# DE-130817_03.net
KiCad netlist of a schematic drawn in Altium Designer
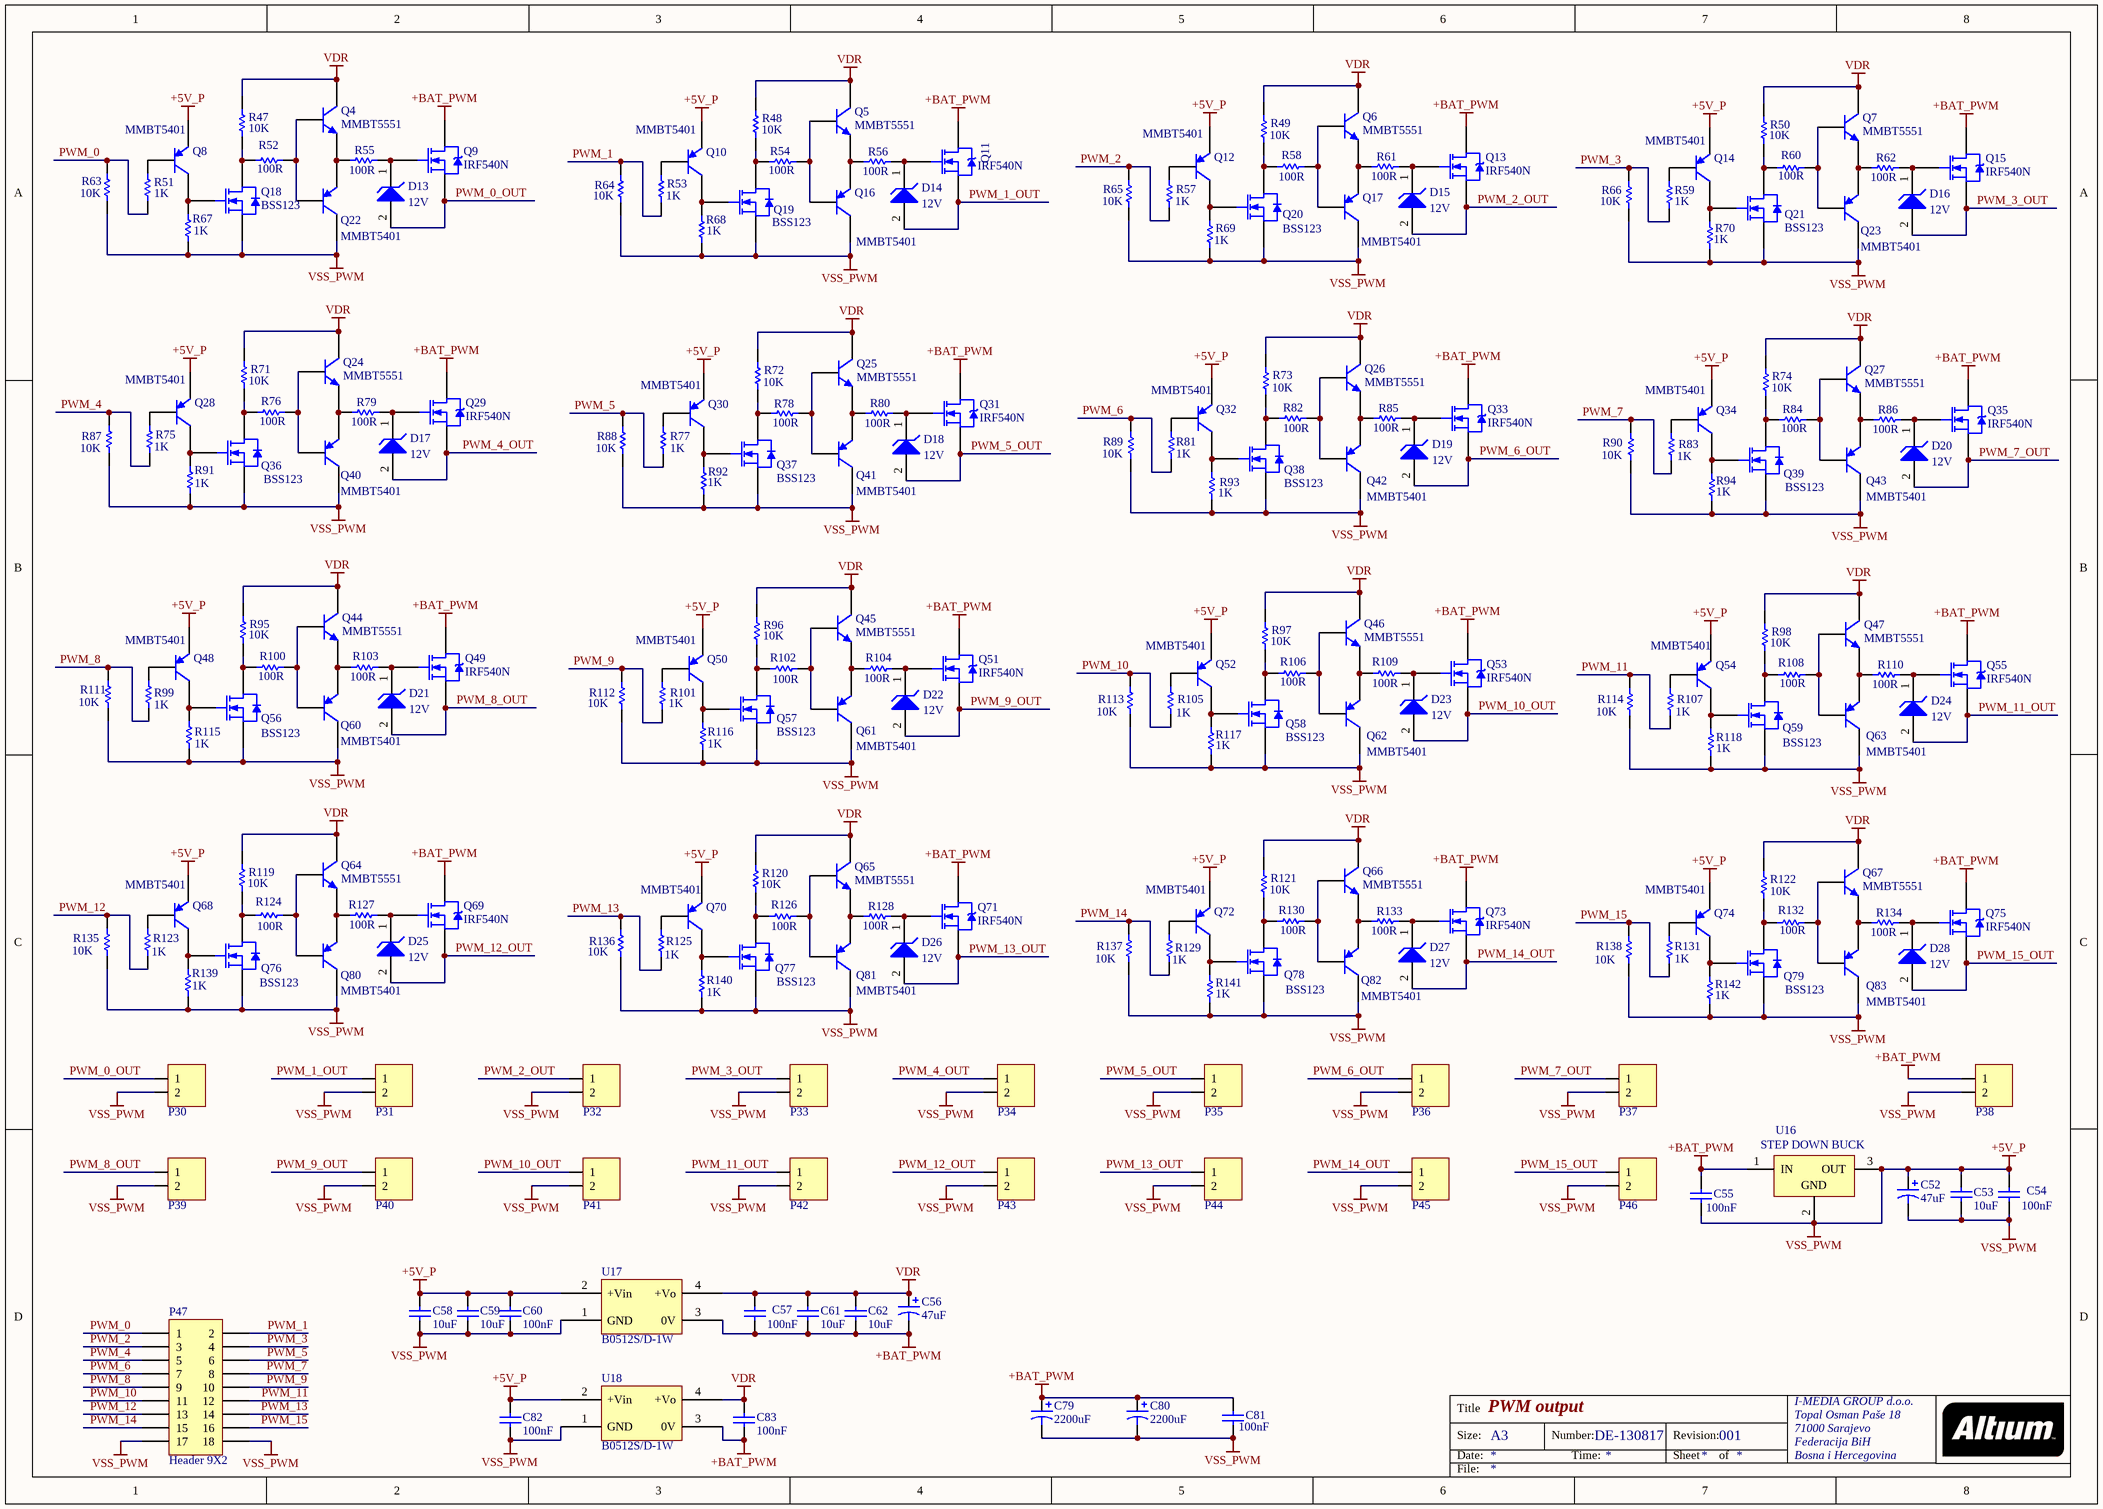
[diagram p0: DE-130817_03.SchDoc]

(export (version "E")
  (design (tool "Eeschema 10.0.6"))
  (components
    (comp (ref "C52")
      (value "47uF")
      (footprint "CAPPR2-5X11")
      (description "Aluminum Electrolytic Capacitor, Radial Style with Long Leads: 47uF, 35V")
      (fields (field (name "Comment") "EKA00AA247F00") (field (name "PUBLISHER") "Altium Limited"))
      (libsource (lib "Vishay Roederstein Electrolytic Radial-Lead Capacitor") (part "EKA00AA247F00"))
    )
    (comp (ref "C53")
      (value "10uF")
      (footprint "0805")
      (description "Ceramic Chip Capacitor - Standard")
      (fields (field (name "PUBLISHER") "Altium Limited"))
      (libsource (lib "DE-130817") (part "C0805"))
    )
    (comp (ref "C54")
      (value "100nF")
      (footprint "0603")
      (description "Ceramic Chip Capacitor - Standard")
      (fields (field (name "PUBLISHER") "Altium Limited"))
      (libsource (lib "DE-130817") (part "C0603"))
    )
    (comp (ref "C55")
      (value "100nF")
      (footprint "VP52-2.5")
      (description "Dipped Radial Multilayer Ceramic Capacitor X7R: 100nF")
      (fields (field (name "Comment") "VP52BY104") (field (name "PUBLISHER") "Altium Limited"))
      (libsource (lib "Vishay Vitramon Ceramic Dipped Capacitor") (part "VP52BY104"))
    )
    (comp (ref "C56")
      (value "47uF")
      (footprint "CAPPR2-5X11")
      (description "Aluminum Electrolytic Capacitor, Radial Style with Long Leads: 47uF, 35V")
      (fields (field (name "Comment") "EKA00AA247F00") (field (name "PUBLISHER") "Altium Limited"))
      (libsource (lib "Vishay Roederstein Electrolytic Radial-Lead Capacitor") (part "EKA00AA247F00"))
    )
    (comp (ref "C57")
      (value "100nF")
      (footprint "0603")
      (description "Ceramic Chip Capacitor - Standard")
      (fields (field (name "PUBLISHER") "Altium Limited"))
      (libsource (lib "DE-130817") (part "C0603"))
    )
    (comp (ref "C58")
      (value "10uF")
      (footprint "0805")
      (description "Ceramic Chip Capacitor - Standard")
      (fields (field (name "PUBLISHER") "Altium Limited"))
      (libsource (lib "DE-130817") (part "C0805"))
    )
    (comp (ref "C59")
      (value "10uF")
      (footprint "0805")
      (description "Ceramic Chip Capacitor - Standard")
      (fields (field (name "PUBLISHER") "Altium Limited"))
      (libsource (lib "DE-130817") (part "C0805"))
    )
    (comp (ref "C60")
      (value "100nF")
      (footprint "0603")
      (description "Ceramic Chip Capacitor - Standard")
      (fields (field (name "PUBLISHER") "Altium Limited"))
      (libsource (lib "DE-130817") (part "C0603"))
    )
    (comp (ref "C61")
      (value "10uF")
      (footprint "0805")
      (description "Ceramic Chip Capacitor - Standard")
      (fields (field (name "PUBLISHER") "Altium Limited"))
      (libsource (lib "DE-130817") (part "C0805"))
    )
    (comp (ref "C62")
      (value "10uF")
      (footprint "0805")
      (description "Ceramic Chip Capacitor - Standard")
      (fields (field (name "PUBLISHER") "Altium Limited"))
      (libsource (lib "DE-130817") (part "C0805"))
    )
    (comp (ref "C79")
      (value "2200uF")
      (footprint "CAPPR7.5-16X35.5")
      (description "Aluminum Electrolytic Capacitor, Radial Style with Long Leads: 2200uF, 50V")
      (fields (field (name "Comment") "EKA00JL422H00") (field (name "PUBLISHER") "Altium Limited"))
      (libsource (lib "Vishay Roederstein Electrolytic Radial-Lead Capacitor") (part "EKA00JL422H00"))
    )
    (comp (ref "C80")
      (value "2200uF")
      (footprint "CAPPR7.5-16X35.5")
      (description "Aluminum Electrolytic Capacitor, Radial Style with Long Leads: 2200uF, 50V")
      (fields (field (name "Comment") "EKA00JL422H00") (field (name "PUBLISHER") "Altium Limited"))
      (libsource (lib "Vishay Roederstein Electrolytic Radial-Lead Capacitor") (part "EKA00JL422H00"))
    )
    (comp (ref "C81")
      (value "100nF")
      (footprint "VP60-3.6")
      (description "Dipped Radial Multilayer Ceramic Capacitor COG (NPO): 100nF, 100V")
      (fields (field (name "Comment") "VP60BA104FB") (field (name "PUBLISHER") "Altium Limited"))
      (libsource (lib "Vishay Vitramon Ceramic Dipped Capacitor") (part "VP60BA104FB"))
    )
    (comp (ref "C82")
      (value "100nF")
      (footprint "0603")
      (description "Ceramic Chip Capacitor - Standard")
      (fields (field (name "PUBLISHER") "Altium Limited"))
      (libsource (lib "DE-130817") (part "C0603"))
    )
    (comp (ref "C83")
      (value "100nF")
      (footprint "0603")
      (description "Ceramic Chip Capacitor - Standard")
      (fields (field (name "PUBLISHER") "Altium Limited"))
      (libsource (lib "DE-130817") (part "C0603"))
    )
    (comp (ref "D13")
      (value "12V")
      (footprint "ONSC-SOD-123-2-425-04_V")
      (description "Zener Voltage Regulator, 500 mW, 2-Pin SOD-123, Pb-Free, Tape and Reel")
      (fields (field (name "MANUFACTURER") "On Semiconductor") (field (name "PARTNUMBER") "SZMMSZ12T1G"))
      (libsource (lib "ON Semi Zener Diodes") (part "SZMMSZ12T1G"))
    )
    (comp (ref "D14")
      (value "12V")
      (footprint "ONSC-SOD-123-2-425-04_V")
      (description "Zener Voltage Regulator, 500 mW, 2-Pin SOD-123, Pb-Free, Tape and Reel")
      (fields (field (name "MANUFACTURER") "On Semiconductor") (field (name "PARTNUMBER") "SZMMSZ12T1G"))
      (libsource (lib "ON Semi Zener Diodes") (part "SZMMSZ12T1G"))
    )
    (comp (ref "D15")
      (value "12V")
      (footprint "ONSC-SOD-123-2-425-04_V")
      (description "Zener Voltage Regulator, 500 mW, 2-Pin SOD-123, Pb-Free, Tape and Reel")
      (fields (field (name "MANUFACTURER") "On Semiconductor") (field (name "PARTNUMBER") "SZMMSZ12T1G"))
      (libsource (lib "ON Semi Zener Diodes") (part "SZMMSZ12T1G"))
    )
    (comp (ref "D16")
      (value "12V")
      (footprint "ONSC-SOD-123-2-425-04_V")
      (description "Zener Voltage Regulator, 500 mW, 2-Pin SOD-123, Pb-Free, Tape and Reel")
      (fields (field (name "MANUFACTURER") "On Semiconductor") (field (name "PARTNUMBER") "SZMMSZ12T1G"))
      (libsource (lib "ON Semi Zener Diodes") (part "SZMMSZ12T1G"))
    )
    (comp (ref "D17")
      (value "12V")
      (footprint "ONSC-SOD-123-2-425-04_V")
      (description "Zener Voltage Regulator, 500 mW, 2-Pin SOD-123, Pb-Free, Tape and Reel")
      (fields (field (name "MANUFACTURER") "On Semiconductor") (field (name "PARTNUMBER") "SZMMSZ12T1G"))
      (libsource (lib "ON Semi Zener Diodes") (part "SZMMSZ12T1G"))
    )
    (comp (ref "D18")
      (value "12V")
      (footprint "ONSC-SOD-123-2-425-04_V")
      (description "Zener Voltage Regulator, 500 mW, 2-Pin SOD-123, Pb-Free, Tape and Reel")
      (fields (field (name "MANUFACTURER") "On Semiconductor") (field (name "PARTNUMBER") "SZMMSZ12T1G"))
      (libsource (lib "ON Semi Zener Diodes") (part "SZMMSZ12T1G"))
    )
    (comp (ref "D19")
      (value "12V")
      (footprint "ONSC-SOD-123-2-425-04_V")
      (description "Zener Voltage Regulator, 500 mW, 2-Pin SOD-123, Pb-Free, Tape and Reel")
      (fields (field (name "MANUFACTURER") "On Semiconductor") (field (name "PARTNUMBER") "SZMMSZ12T1G"))
      (libsource (lib "ON Semi Zener Diodes") (part "SZMMSZ12T1G"))
    )
    (comp (ref "D20")
      (value "12V")
      (footprint "ONSC-SOD-123-2-425-04_V")
      (description "Zener Voltage Regulator, 500 mW, 2-Pin SOD-123, Pb-Free, Tape and Reel")
      (fields (field (name "MANUFACTURER") "On Semiconductor") (field (name "PARTNUMBER") "SZMMSZ12T1G"))
      (libsource (lib "ON Semi Zener Diodes") (part "SZMMSZ12T1G"))
    )
    (comp (ref "D21")
      (value "12V")
      (footprint "ONSC-SOD-123-2-425-04_V")
      (description "Zener Voltage Regulator, 500 mW, 2-Pin SOD-123, Pb-Free, Tape and Reel")
      (fields (field (name "MANUFACTURER") "On Semiconductor") (field (name "PARTNUMBER") "SZMMSZ12T1G"))
      (libsource (lib "ON Semi Zener Diodes") (part "SZMMSZ12T1G"))
    )
    (comp (ref "D22")
      (value "12V")
      (footprint "ONSC-SOD-123-2-425-04_V")
      (description "Zener Voltage Regulator, 500 mW, 2-Pin SOD-123, Pb-Free, Tape and Reel")
      (fields (field (name "MANUFACTURER") "On Semiconductor") (field (name "PARTNUMBER") "SZMMSZ12T1G"))
      (libsource (lib "ON Semi Zener Diodes") (part "SZMMSZ12T1G"))
    )
    (comp (ref "D23")
      (value "12V")
      (footprint "ONSC-SOD-123-2-425-04_V")
      (description "Zener Voltage Regulator, 500 mW, 2-Pin SOD-123, Pb-Free, Tape and Reel")
      (fields (field (name "MANUFACTURER") "On Semiconductor") (field (name "PARTNUMBER") "SZMMSZ12T1G"))
      (libsource (lib "ON Semi Zener Diodes") (part "SZMMSZ12T1G"))
    )
    (comp (ref "D24")
      (value "12V")
      (footprint "ONSC-SOD-123-2-425-04_V")
      (description "Zener Voltage Regulator, 500 mW, 2-Pin SOD-123, Pb-Free, Tape and Reel")
      (fields (field (name "MANUFACTURER") "On Semiconductor") (field (name "PARTNUMBER") "SZMMSZ12T1G"))
      (libsource (lib "ON Semi Zener Diodes") (part "SZMMSZ12T1G"))
    )
    (comp (ref "D25")
      (value "12V")
      (footprint "ONSC-SOD-123-2-425-04_V")
      (description "Zener Voltage Regulator, 500 mW, 2-Pin SOD-123, Pb-Free, Tape and Reel")
      (fields (field (name "MANUFACTURER") "On Semiconductor") (field (name "PARTNUMBER") "SZMMSZ12T1G"))
      (libsource (lib "ON Semi Zener Diodes") (part "SZMMSZ12T1G"))
    )
    (comp (ref "D26")
      (value "12V")
      (footprint "ONSC-SOD-123-2-425-04_V")
      (description "Zener Voltage Regulator, 500 mW, 2-Pin SOD-123, Pb-Free, Tape and Reel")
      (fields (field (name "MANUFACTURER") "On Semiconductor") (field (name "PARTNUMBER") "SZMMSZ12T1G"))
      (libsource (lib "ON Semi Zener Diodes") (part "SZMMSZ12T1G"))
    )
    (comp (ref "D27")
      (value "12V")
      (footprint "ONSC-SOD-123-2-425-04_V")
      (description "Zener Voltage Regulator, 500 mW, 2-Pin SOD-123, Pb-Free, Tape and Reel")
      (fields (field (name "MANUFACTURER") "On Semiconductor") (field (name "PARTNUMBER") "SZMMSZ12T1G"))
      (libsource (lib "ON Semi Zener Diodes") (part "SZMMSZ12T1G"))
    )
    (comp (ref "D28")
      (value "12V")
      (footprint "ONSC-SOD-123-2-425-04_V")
      (description "Zener Voltage Regulator, 500 mW, 2-Pin SOD-123, Pb-Free, Tape and Reel")
      (fields (field (name "MANUFACTURER") "On Semiconductor") (field (name "PARTNUMBER") "SZMMSZ12T1G"))
      (libsource (lib "ON Semi Zener Diodes") (part "SZMMSZ12T1G"))
    )
    (comp (ref "P30")
      (value "TERMINAL BLOK 2")
      (footprint "TERMINAL BLOK 2")
      (description "2 pinski terminal blok")
      (libsource (lib "DE-130817") (part "TERMINAL BLOK 2"))
    )
    (comp (ref "P31")
      (value "TERMINAL BLOK 2")
      (footprint "TERMINAL BLOK 2")
      (description "2 pinski terminal blok")
      (libsource (lib "DE-130817") (part "TERMINAL BLOK 2"))
    )
    (comp (ref "P32")
      (value "TERMINAL BLOK 2")
      (footprint "TERMINAL BLOK 2")
      (description "2 pinski terminal blok")
      (libsource (lib "DE-130817") (part "TERMINAL BLOK 2"))
    )
    (comp (ref "P33")
      (value "TERMINAL BLOK 2")
      (footprint "TERMINAL BLOK 2")
      (description "2 pinski terminal blok")
      (libsource (lib "DE-130817") (part "TERMINAL BLOK 2"))
    )
    (comp (ref "P34")
      (value "TERMINAL BLOK 2")
      (footprint "TERMINAL BLOK 2")
      (description "2 pinski terminal blok")
      (libsource (lib "DE-130817") (part "TERMINAL BLOK 2"))
    )
    (comp (ref "P35")
      (value "TERMINAL BLOK 2")
      (footprint "TERMINAL BLOK 2")
      (description "2 pinski terminal blok")
      (libsource (lib "") (part "TERMINAL BLOK 2_3"))
    )
    (comp (ref "P36")
      (value "TERMINAL BLOK 2")
      (footprint "TERMINAL BLOK 2")
      (description "2 pinski terminal blok")
      (libsource (lib "") (part "TERMINAL BLOK 2_3"))
    )
    (comp (ref "P37")
      (value "TERMINAL BLOK 2")
      (footprint "TERMINAL BLOK 2")
      (description "2 pinski terminal blok")
      (libsource (lib "") (part "TERMINAL BLOK 2_3"))
    )
    (comp (ref "P38")
      (value "TERMINAL BLOK 2")
      (footprint "TERMINAL BLOK 2")
      (description "2 pinski terminal blok")
      (libsource (lib "") (part "TERMINAL BLOK 2_3"))
    )
    (comp (ref "P39")
      (value "TERMINAL BLOK 2")
      (footprint "TERMINAL BLOK 2")
      (description "2 pinski terminal blok")
      (libsource (lib "") (part "TERMINAL BLOK 2_1"))
    )
    (comp (ref "P40")
      (value "TERMINAL BLOK 2")
      (footprint "TERMINAL BLOK 2")
      (description "2 pinski terminal blok")
      (libsource (lib "") (part "TERMINAL BLOK 2_1"))
    )
    (comp (ref "P41")
      (value "TERMINAL BLOK 2")
      (footprint "TERMINAL BLOK 2")
      (description "2 pinski terminal blok")
      (libsource (lib "") (part "TERMINAL BLOK 2_1"))
    )
    (comp (ref "P42")
      (value "TERMINAL BLOK 2")
      (footprint "TERMINAL BLOK 2")
      (description "2 pinski terminal blok")
      (libsource (lib "") (part "TERMINAL BLOK 2_1"))
    )
    (comp (ref "P43")
      (value "TERMINAL BLOK 2")
      (footprint "TERMINAL BLOK 2")
      (description "2 pinski terminal blok")
      (libsource (lib "") (part "TERMINAL BLOK 2_1"))
    )
    (comp (ref "P44")
      (value "TERMINAL BLOK 2")
      (footprint "TERMINAL BLOK 2")
      (description "2 pinski terminal blok")
      (libsource (lib "") (part "TERMINAL BLOK 2_2"))
    )
    (comp (ref "P45")
      (value "TERMINAL BLOK 2")
      (footprint "TERMINAL BLOK 2")
      (description "2 pinski terminal blok")
      (libsource (lib "") (part "TERMINAL BLOK 2_2"))
    )
    (comp (ref "P46")
      (value "TERMINAL BLOK 2")
      (footprint "TERMINAL BLOK 2")
      (description "2 pinski terminal blok")
      (libsource (lib "") (part "TERMINAL BLOK 2_2"))
    )
    (comp (ref "P47")
      (value "Header 9X2")
      (footprint "HDR2X9")
      (description "Header, 9-Pin, Dual row")
      (fields (field (name "PUBLISHER") "Altium Limited"))
      (libsource (lib "Miscellaneous Connectors") (part "Header 9X2"))
    )
    (comp (ref "Q4")
      (value "MMBT5551")
      (footprint "SOT23_N")
      (description "NPN General-purpose Transistor")
      (fields (field (name "PUBLISHER") "Altium Limited"))
      (libsource (lib "DE-130817") (part "BC817"))
    )
    (comp (ref "Q5")
      (value "MMBT5551")
      (footprint "SOT23_N")
      (description "NPN General-purpose Transistor")
      (fields (field (name "PUBLISHER") "Altium Limited"))
      (libsource (lib "DE-130817") (part "BC817"))
    )
    (comp (ref "Q6")
      (value "MMBT5551")
      (footprint "SOT23_N")
      (description "NPN General-purpose Transistor")
      (fields (field (name "PUBLISHER") "Altium Limited"))
      (libsource (lib "DE-130817") (part "BC817"))
    )
    (comp (ref "Q7")
      (value "MMBT5551")
      (footprint "SOT23_N")
      (description "NPN General-purpose Transistor")
      (fields (field (name "PUBLISHER") "Altium Limited"))
      (libsource (lib "DE-130817") (part "BC817"))
    )
    (comp (ref "Q8")
      (value "MMBT5401")
      (footprint "SOT23_N")
      (description "PNP General-purpose Transistor")
      (fields (field (name "PUBLISHER") "Altium Limited"))
      (libsource (lib "DE-130817") (part "BC807"))
    )
    (comp (ref "Q9")
      (value "IRF540N")
      (footprint "TO-220AB")
      (description "HEXFET Power MOSFET")
      (fields (field (name "PUBLISHER") "Altium Limited"))
      (libsource (lib "IR Discrete MOSFET - Power") (part "IRF540N"))
    )
    (comp (ref "Q10")
      (value "MMBT5401")
      (footprint "SOT23_N")
      (description "PNP General-purpose Transistor")
      (fields (field (name "PUBLISHER") "Altium Limited"))
      (libsource (lib "DE-130817") (part "BC807"))
    )
    (comp (ref "Q11")
      (value "IRF540N")
      (footprint "TO-220AB")
      (description "HEXFET Power MOSFET")
      (fields (field (name "PUBLISHER") "Altium Limited"))
      (libsource (lib "IR Discrete MOSFET - Power") (part "IRF540N"))
    )
    (comp (ref "Q12")
      (value "MMBT5401")
      (footprint "SOT23_N")
      (description "PNP General-purpose Transistor")
      (fields (field (name "PUBLISHER") "Altium Limited"))
      (libsource (lib "DE-130817") (part "BC807"))
    )
    (comp (ref "Q13")
      (value "IRF540N")
      (footprint "TO-220AB")
      (description "HEXFET Power MOSFET")
      (fields (field (name "PUBLISHER") "Altium Limited"))
      (libsource (lib "IR Discrete MOSFET - Power") (part "IRF540N"))
    )
    (comp (ref "Q14")
      (value "MMBT5401")
      (footprint "SOT23_N")
      (description "PNP General-purpose Transistor")
      (fields (field (name "PUBLISHER") "Altium Limited"))
      (libsource (lib "DE-130817") (part "BC807"))
    )
    (comp (ref "Q15")
      (value "IRF540N")
      (footprint "TO-220AB")
      (description "HEXFET Power MOSFET")
      (fields (field (name "PUBLISHER") "Altium Limited"))
      (libsource (lib "IR Discrete MOSFET - Power") (part "IRF540N"))
    )
    (comp (ref "Q16")
      (value "MMBT5401")
      (footprint "SOT23_N")
      (description "PNP General-purpose Transistor")
      (fields (field (name "PUBLISHER") "Altium Limited"))
      (libsource (lib "DE-130817") (part "BC807"))
    )
    (comp (ref "Q17")
      (value "MMBT5401")
      (footprint "SOT23_N")
      (description "PNP General-purpose Transistor")
      (fields (field (name "PUBLISHER") "Altium Limited"))
      (libsource (lib "DE-130817") (part "BC807"))
    )
    (comp (ref "Q18")
      (value "BSS123")
      (footprint "SOT23_N")
      (description "N-channel Enhancement Mode Vertical D-MOSFET")
      (fields (field (name "PUBLISHER") "Altium Limited"))
      (libsource (lib "sch_library") (part "BSS123"))
    )
    (comp (ref "Q19")
      (value "BSS123")
      (footprint "SOT23_N")
      (description "N-channel Enhancement Mode Vertical D-MOSFET")
      (fields (field (name "PUBLISHER") "Altium Limited"))
      (libsource (lib "sch_library") (part "BSS123"))
    )
    (comp (ref "Q20")
      (value "BSS123")
      (footprint "SOT23_N")
      (description "N-channel Enhancement Mode Vertical D-MOSFET")
      (fields (field (name "PUBLISHER") "Altium Limited"))
      (libsource (lib "sch_library") (part "BSS123"))
    )
    (comp (ref "Q21")
      (value "BSS123")
      (footprint "SOT23_N")
      (description "N-channel Enhancement Mode Vertical D-MOSFET")
      (fields (field (name "PUBLISHER") "Altium Limited"))
      (libsource (lib "sch_library") (part "BSS123"))
    )
    (comp (ref "Q22")
      (value "MMBT5401")
      (footprint "SOT23_N")
      (description "PNP General-purpose Transistor")
      (fields (field (name "PUBLISHER") "Altium Limited"))
      (libsource (lib "DE-130817") (part "BC807"))
    )
    (comp (ref "Q23")
      (value "MMBT5401")
      (footprint "SOT23_N")
      (description "PNP General-purpose Transistor")
      (fields (field (name "PUBLISHER") "Altium Limited"))
      (libsource (lib "DE-130817") (part "BC807"))
    )
    (comp (ref "Q24")
      (value "MMBT5551")
      (footprint "SOT23_N")
      (description "NPN General-purpose Transistor")
      (fields (field (name "PUBLISHER") "Altium Limited"))
      (libsource (lib "DE-130817") (part "BC817"))
    )
    (comp (ref "Q25")
      (value "MMBT5551")
      (footprint "SOT23_N")
      (description "NPN General-purpose Transistor")
      (fields (field (name "PUBLISHER") "Altium Limited"))
      (libsource (lib "DE-130817") (part "BC817"))
    )
    (comp (ref "Q26")
      (value "MMBT5551")
      (footprint "SOT23_N")
      (description "NPN General-purpose Transistor")
      (fields (field (name "PUBLISHER") "Altium Limited"))
      (libsource (lib "DE-130817") (part "BC817"))
    )
    (comp (ref "Q27")
      (value "MMBT5551")
      (footprint "SOT23_N")
      (description "NPN General-purpose Transistor")
      (fields (field (name "PUBLISHER") "Altium Limited"))
      (libsource (lib "DE-130817") (part "BC817"))
    )
    (comp (ref "Q28")
      (value "MMBT5401")
      (footprint "SOT23_N")
      (description "PNP General-purpose Transistor")
      (fields (field (name "PUBLISHER") "Altium Limited"))
      (libsource (lib "DE-130817") (part "BC807"))
    )
    (comp (ref "Q29")
      (value "IRF540N")
      (footprint "TO-220AB")
      (description "HEXFET Power MOSFET")
      (fields (field (name "PUBLISHER") "Altium Limited"))
      (libsource (lib "IR Discrete MOSFET - Power") (part "IRF540N"))
    )
    (comp (ref "Q30")
      (value "MMBT5401")
      (footprint "SOT23_N")
      (description "PNP General-purpose Transistor")
      (fields (field (name "PUBLISHER") "Altium Limited"))
      (libsource (lib "DE-130817") (part "BC807"))
    )
    (comp (ref "Q31")
      (value "IRF540N")
      (footprint "TO-220AB")
      (description "HEXFET Power MOSFET")
      (fields (field (name "PUBLISHER") "Altium Limited"))
      (libsource (lib "IR Discrete MOSFET - Power") (part "IRF540N"))
    )
    (comp (ref "Q32")
      (value "MMBT5401")
      (footprint "SOT23_N")
      (description "PNP General-purpose Transistor")
      (fields (field (name "PUBLISHER") "Altium Limited"))
      (libsource (lib "DE-130817") (part "BC807"))
    )
    (comp (ref "Q33")
      (value "IRF540N")
      (footprint "TO-220AB")
      (description "HEXFET Power MOSFET")
      (fields (field (name "PUBLISHER") "Altium Limited"))
      (libsource (lib "IR Discrete MOSFET - Power") (part "IRF540N"))
    )
    (comp (ref "Q34")
      (value "MMBT5401")
      (footprint "SOT23_N")
      (description "PNP General-purpose Transistor")
      (fields (field (name "PUBLISHER") "Altium Limited"))
      (libsource (lib "DE-130817") (part "BC807"))
    )
    (comp (ref "Q35")
      (value "IRF540N")
      (footprint "TO-220AB")
      (description "HEXFET Power MOSFET")
      (fields (field (name "PUBLISHER") "Altium Limited"))
      (libsource (lib "IR Discrete MOSFET - Power") (part "IRF540N"))
    )
    (comp (ref "Q36")
      (value "BSS123")
      (footprint "SOT23_N")
      (description "N-channel Enhancement Mode Vertical D-MOSFET")
      (fields (field (name "PUBLISHER") "Altium Limited"))
      (libsource (lib "sch_library") (part "BSS123"))
    )
    (comp (ref "Q37")
      (value "BSS123")
      (footprint "SOT23_N")
      (description "N-channel Enhancement Mode Vertical D-MOSFET")
      (fields (field (name "PUBLISHER") "Altium Limited"))
      (libsource (lib "sch_library") (part "BSS123"))
    )
    (comp (ref "Q38")
      (value "BSS123")
      (footprint "SOT23_N")
      (description "N-channel Enhancement Mode Vertical D-MOSFET")
      (fields (field (name "PUBLISHER") "Altium Limited"))
      (libsource (lib "sch_library") (part "BSS123"))
    )
    (comp (ref "Q39")
      (value "BSS123")
      (footprint "SOT23_N")
      (description "N-channel Enhancement Mode Vertical D-MOSFET")
      (fields (field (name "PUBLISHER") "Altium Limited"))
      (libsource (lib "sch_library") (part "BSS123"))
    )
    (comp (ref "Q40")
      (value "MMBT5401")
      (footprint "SOT23_N")
      (description "PNP General-purpose Transistor")
      (fields (field (name "PUBLISHER") "Altium Limited"))
      (libsource (lib "DE-130817") (part "BC807"))
    )
    (comp (ref "Q41")
      (value "MMBT5401")
      (footprint "SOT23_N")
      (description "PNP General-purpose Transistor")
      (fields (field (name "PUBLISHER") "Altium Limited"))
      (libsource (lib "DE-130817") (part "BC807"))
    )
    (comp (ref "Q42")
      (value "MMBT5401")
      (footprint "SOT23_N")
      (description "PNP General-purpose Transistor")
      (fields (field (name "PUBLISHER") "Altium Limited"))
      (libsource (lib "DE-130817") (part "BC807"))
    )
    (comp (ref "Q43")
      (value "MMBT5401")
      (footprint "SOT23_N")
      (description "PNP General-purpose Transistor")
      (fields (field (name "PUBLISHER") "Altium Limited"))
      (libsource (lib "DE-130817") (part "BC807"))
    )
    (comp (ref "Q44")
      (value "MMBT5551")
      (footprint "SOT23_N")
      (description "NPN General-purpose Transistor")
      (fields (field (name "PUBLISHER") "Altium Limited"))
      (libsource (lib "DE-130817") (part "BC817"))
    )
    (comp (ref "Q45")
      (value "MMBT5551")
      (footprint "SOT23_N")
      (description "NPN General-purpose Transistor")
      (fields (field (name "PUBLISHER") "Altium Limited"))
      (libsource (lib "DE-130817") (part "BC817"))
    )
    (comp (ref "Q46")
      (value "MMBT5551")
      (footprint "SOT23_N")
      (description "NPN General-purpose Transistor")
      (fields (field (name "PUBLISHER") "Altium Limited"))
      (libsource (lib "DE-130817") (part "BC817"))
    )
    (comp (ref "Q47")
      (value "MMBT5551")
      (footprint "SOT23_N")
      (description "NPN General-purpose Transistor")
      (fields (field (name "PUBLISHER") "Altium Limited"))
      (libsource (lib "DE-130817") (part "BC817"))
    )
    (comp (ref "Q48")
      (value "MMBT5401")
      (footprint "SOT23_N")
      (description "PNP General-purpose Transistor")
      (fields (field (name "PUBLISHER") "Altium Limited"))
      (libsource (lib "DE-130817") (part "BC807"))
    )
    (comp (ref "Q49")
      (value "IRF540N")
      (footprint "TO-220AB")
      (description "HEXFET Power MOSFET")
      (fields (field (name "PUBLISHER") "Altium Limited"))
      (libsource (lib "IR Discrete MOSFET - Power") (part "IRF540N"))
    )
    (comp (ref "Q50")
      (value "MMBT5401")
      (footprint "SOT23_N")
      (description "PNP General-purpose Transistor")
      (fields (field (name "PUBLISHER") "Altium Limited"))
      (libsource (lib "DE-130817") (part "BC807"))
    )
    (comp (ref "Q51")
      (value "IRF540N")
      (footprint "TO-220AB")
      (description "HEXFET Power MOSFET")
      (fields (field (name "PUBLISHER") "Altium Limited"))
      (libsource (lib "IR Discrete MOSFET - Power") (part "IRF540N"))
    )
    (comp (ref "Q52")
      (value "MMBT5401")
      (footprint "SOT23_N")
      (description "PNP General-purpose Transistor")
      (fields (field (name "PUBLISHER") "Altium Limited"))
      (libsource (lib "DE-130817") (part "BC807"))
    )
    (comp (ref "Q53")
      (value "IRF540N")
      (footprint "TO-220AB")
      (description "HEXFET Power MOSFET")
      (fields (field (name "PUBLISHER") "Altium Limited"))
      (libsource (lib "IR Discrete MOSFET - Power") (part "IRF540N"))
    )
    (comp (ref "Q54")
      (value "MMBT5401")
      (footprint "SOT23_N")
      (description "PNP General-purpose Transistor")
      (fields (field (name "PUBLISHER") "Altium Limited"))
      (libsource (lib "DE-130817") (part "BC807"))
    )
    (comp (ref "Q55")
      (value "IRF540N")
      (footprint "TO-220AB")
      (description "HEXFET Power MOSFET")
      (fields (field (name "PUBLISHER") "Altium Limited"))
      (libsource (lib "IR Discrete MOSFET - Power") (part "IRF540N"))
    )
    (comp (ref "Q56")
      (value "BSS123")
      (footprint "SOT23_N")
      (description "N-channel Enhancement Mode Vertical D-MOSFET")
      (fields (field (name "PUBLISHER") "Altium Limited"))
      (libsource (lib "sch_library") (part "BSS123"))
    )
    (comp (ref "Q57")
      (value "BSS123")
      (footprint "SOT23_N")
      (description "N-channel Enhancement Mode Vertical D-MOSFET")
      (fields (field (name "PUBLISHER") "Altium Limited"))
      (libsource (lib "sch_library") (part "BSS123"))
    )
    (comp (ref "Q58")
      (value "BSS123")
      (footprint "SOT23_N")
      (description "N-channel Enhancement Mode Vertical D-MOSFET")
      (fields (field (name "PUBLISHER") "Altium Limited"))
      (libsource (lib "sch_library") (part "BSS123"))
    )
    (comp (ref "Q59")
      (value "BSS123")
      (footprint "SOT23_N")
      (description "N-channel Enhancement Mode Vertical D-MOSFET")
      (fields (field (name "PUBLISHER") "Altium Limited"))
      (libsource (lib "sch_library") (part "BSS123"))
    )
    (comp (ref "Q60")
      (value "MMBT5401")
      (footprint "SOT23_N")
      (description "PNP General-purpose Transistor")
      (fields (field (name "PUBLISHER") "Altium Limited"))
      (libsource (lib "DE-130817") (part "BC807"))
    )
    (comp (ref "Q61")
      (value "MMBT5401")
      (footprint "SOT23_N")
      (description "PNP General-purpose Transistor")
      (fields (field (name "PUBLISHER") "Altium Limited"))
      (libsource (lib "DE-130817") (part "BC807"))
    )
    (comp (ref "Q62")
      (value "MMBT5401")
      (footprint "SOT23_N")
      (description "PNP General-purpose Transistor")
      (fields (field (name "PUBLISHER") "Altium Limited"))
      (libsource (lib "DE-130817") (part "BC807"))
    )
    (comp (ref "Q63")
      (value "MMBT5401")
      (footprint "SOT23_N")
      (description "PNP General-purpose Transistor")
      (fields (field (name "PUBLISHER") "Altium Limited"))
      (libsource (lib "DE-130817") (part "BC807"))
    )
    (comp (ref "Q64")
      (value "MMBT5551")
      (footprint "SOT23_N")
      (description "NPN General-purpose Transistor")
      (fields (field (name "PUBLISHER") "Altium Limited"))
      (libsource (lib "DE-130817") (part "BC817"))
    )
    (comp (ref "Q65")
      (value "MMBT5551")
      (footprint "SOT23_N")
      (description "NPN General-purpose Transistor")
      (fields (field (name "PUBLISHER") "Altium Limited"))
      (libsource (lib "DE-130817") (part "BC817"))
    )
    (comp (ref "Q66")
      (value "MMBT5551")
      (footprint "SOT23_N")
      (description "NPN General-purpose Transistor")
      (fields (field (name "PUBLISHER") "Altium Limited"))
      (libsource (lib "DE-130817") (part "BC817"))
    )
    (comp (ref "Q67")
      (value "MMBT5551")
      (footprint "SOT23_N")
      (description "NPN General-purpose Transistor")
      (fields (field (name "PUBLISHER") "Altium Limited"))
      (libsource (lib "DE-130817") (part "BC817"))
    )
    (comp (ref "Q68")
      (value "MMBT5401")
      (footprint "SOT23_N")
      (description "PNP General-purpose Transistor")
      (fields (field (name "PUBLISHER") "Altium Limited"))
      (libsource (lib "DE-130817") (part "BC807"))
    )
    (comp (ref "Q69")
      (value "IRF540N")
      (footprint "TO-220AB")
      (description "HEXFET Power MOSFET")
      (fields (field (name "PUBLISHER") "Altium Limited"))
      (libsource (lib "IR Discrete MOSFET - Power") (part "IRF540N"))
    )
    (comp (ref "Q70")
      (value "MMBT5401")
      (footprint "SOT23_N")
      (description "PNP General-purpose Transistor")
      (fields (field (name "PUBLISHER") "Altium Limited"))
      (libsource (lib "DE-130817") (part "BC807"))
    )
    (comp (ref "Q71")
      (value "IRF540N")
      (footprint "TO-220AB")
      (description "HEXFET Power MOSFET")
      (fields (field (name "PUBLISHER") "Altium Limited"))
      (libsource (lib "IR Discrete MOSFET - Power") (part "IRF540N"))
    )
    (comp (ref "Q72")
      (value "MMBT5401")
      (footprint "SOT23_N")
      (description "PNP General-purpose Transistor")
      (fields (field (name "PUBLISHER") "Altium Limited"))
      (libsource (lib "DE-130817") (part "BC807"))
    )
    (comp (ref "Q73")
      (value "IRF540N")
      (footprint "TO-220AB")
      (description "HEXFET Power MOSFET")
      (fields (field (name "PUBLISHER") "Altium Limited"))
      (libsource (lib "IR Discrete MOSFET - Power") (part "IRF540N"))
    )
    (comp (ref "Q74")
      (value "MMBT5401")
      (footprint "SOT23_N")
      (description "PNP General-purpose Transistor")
      (fields (field (name "PUBLISHER") "Altium Limited"))
      (libsource (lib "DE-130817") (part "BC807"))
    )
    (comp (ref "Q75")
      (value "IRF540N")
      (footprint "TO-220AB")
      (description "HEXFET Power MOSFET")
      (fields (field (name "PUBLISHER") "Altium Limited"))
      (libsource (lib "IR Discrete MOSFET - Power") (part "IRF540N"))
    )
    (comp (ref "Q76")
      (value "BSS123")
      (footprint "SOT23_N")
      (description "N-channel Enhancement Mode Vertical D-MOSFET")
      (fields (field (name "PUBLISHER") "Altium Limited"))
      (libsource (lib "sch_library") (part "BSS123"))
    )
    (comp (ref "Q77")
      (value "BSS123")
      (footprint "SOT23_N")
      (description "N-channel Enhancement Mode Vertical D-MOSFET")
      (fields (field (name "PUBLISHER") "Altium Limited"))
      (libsource (lib "sch_library") (part "BSS123"))
    )
    (comp (ref "Q78")
      (value "BSS123")
      (footprint "SOT23_N")
      (description "N-channel Enhancement Mode Vertical D-MOSFET")
      (fields (field (name "PUBLISHER") "Altium Limited"))
      (libsource (lib "sch_library") (part "BSS123"))
    )
    (comp (ref "Q79")
      (value "BSS123")
      (footprint "SOT23_N")
      (description "N-channel Enhancement Mode Vertical D-MOSFET")
      (fields (field (name "PUBLISHER") "Altium Limited"))
      (libsource (lib "sch_library") (part "BSS123"))
    )
    (comp (ref "Q80")
      (value "MMBT5401")
      (footprint "SOT23_N")
      (description "PNP General-purpose Transistor")
      (fields (field (name "PUBLISHER") "Altium Limited"))
      (libsource (lib "DE-130817") (part "BC807"))
    )
    (comp (ref "Q81")
      (value "MMBT5401")
      (footprint "SOT23_N")
      (description "PNP General-purpose Transistor")
      (fields (field (name "PUBLISHER") "Altium Limited"))
      (libsource (lib "DE-130817") (part "BC807"))
    )
    (comp (ref "Q82")
      (value "MMBT5401")
      (footprint "SOT23_N")
      (description "PNP General-purpose Transistor")
      (fields (field (name "PUBLISHER") "Altium Limited"))
      (libsource (lib "DE-130817") (part "BC807"))
    )
    (comp (ref "Q83")
      (value "MMBT5401")
      (footprint "SOT23_N")
      (description "PNP General-purpose Transistor")
      (fields (field (name "PUBLISHER") "Altium Limited"))
      (libsource (lib "DE-130817") (part "BC807"))
    )
    (comp (ref "R47")
      (value "10K")
      (footprint "12-1812")
      (description "Thick Film Chip Resistor, 1 Ohm to 10M Ohm Range, 5% Tolerance, 1812 Size, 0.5 W")
      (fields (field (name "PUBLISHER") "Altium Limited"))
      (libsource (lib "Panasonic Resistor") (part "ERJ12"))
    )
    (comp (ref "R48")
      (value "10K")
      (footprint "12-1812")
      (description "Thick Film Chip Resistor, 1 Ohm to 10M Ohm Range, 5% Tolerance, 1812 Size, 0.5 W")
      (fields (field (name "PUBLISHER") "Altium Limited"))
      (libsource (lib "Panasonic Resistor") (part "ERJ12"))
    )
    (comp (ref "R49")
      (value "10K")
      (footprint "12-1812")
      (description "Thick Film Chip Resistor, 1 Ohm to 10M Ohm Range, 5% Tolerance, 1812 Size, 0.5 W")
      (fields (field (name "PUBLISHER") "Altium Limited"))
      (libsource (lib "Panasonic Resistor") (part "ERJ12"))
    )
    (comp (ref "R50")
      (value "10K")
      (footprint "12-1812")
      (description "Thick Film Chip Resistor, 1 Ohm to 10M Ohm Range, 5% Tolerance, 1812 Size, 0.5 W")
      (fields (field (name "PUBLISHER") "Altium Limited"))
      (libsource (lib "Panasonic Resistor") (part "ERJ12"))
    )
    (comp (ref "R51")
      (value "1K")
      (footprint "ERA-0805")
      (fields (field (name "PUBLISHER") "Altium Limited"))
      (libsource (lib "Panasonic Resistor") (part "ERA6Y"))
    )
    (comp (ref "R52")
      (value "100R")
      (footprint "ERA-0805")
      (fields (field (name "PUBLISHER") "Altium Limited"))
      (libsource (lib "Panasonic Resistor") (part "ERA6Y"))
    )
    (comp (ref "R53")
      (value "1K")
      (footprint "ERA-0805")
      (fields (field (name "PUBLISHER") "Altium Limited"))
      (libsource (lib "Panasonic Resistor") (part "ERA6Y"))
    )
    (comp (ref "R54")
      (value "100R")
      (footprint "ERA-0805")
      (fields (field (name "PUBLISHER") "Altium Limited"))
      (libsource (lib "Panasonic Resistor") (part "ERA6Y"))
    )
    (comp (ref "R55")
      (value "100R")
      (footprint "ERA-0805")
      (fields (field (name "PUBLISHER") "Altium Limited"))
      (libsource (lib "Panasonic Resistor") (part "ERA6Y"))
    )
    (comp (ref "R56")
      (value "100R")
      (footprint "ERA-0805")
      (fields (field (name "PUBLISHER") "Altium Limited"))
      (libsource (lib "Panasonic Resistor") (part "ERA6Y"))
    )
    (comp (ref "R57")
      (value "1K")
      (footprint "ERA-0805")
      (fields (field (name "PUBLISHER") "Altium Limited"))
      (libsource (lib "Panasonic Resistor") (part "ERA6Y"))
    )
    (comp (ref "R58")
      (value "100R")
      (footprint "ERA-0805")
      (fields (field (name "PUBLISHER") "Altium Limited"))
      (libsource (lib "Panasonic Resistor") (part "ERA6Y"))
    )
    (comp (ref "R59")
      (value "1K")
      (footprint "ERA-0805")
      (fields (field (name "PUBLISHER") "Altium Limited"))
      (libsource (lib "Panasonic Resistor") (part "ERA6Y"))
    )
    (comp (ref "R60")
      (value "100R")
      (footprint "ERA-0805")
      (fields (field (name "PUBLISHER") "Altium Limited"))
      (libsource (lib "Panasonic Resistor") (part "ERA6Y"))
    )
    (comp (ref "R61")
      (value "100R")
      (footprint "ERA-0805")
      (fields (field (name "PUBLISHER") "Altium Limited"))
      (libsource (lib "Panasonic Resistor") (part "ERA6Y"))
    )
    (comp (ref "R62")
      (value "100R")
      (footprint "ERA-0805")
      (fields (field (name "PUBLISHER") "Altium Limited"))
      (libsource (lib "Panasonic Resistor") (part "ERA6Y"))
    )
    (comp (ref "R63")
      (value "10K")
      (footprint "ERA-0805")
      (fields (field (name "PUBLISHER") "Altium Limited"))
      (libsource (lib "Panasonic Resistor") (part "ERA6Y"))
    )
    (comp (ref "R64")
      (value "10K")
      (footprint "ERA-0805")
      (fields (field (name "PUBLISHER") "Altium Limited"))
      (libsource (lib "Panasonic Resistor") (part "ERA6Y"))
    )
    (comp (ref "R65")
      (value "10K")
      (footprint "ERA-0805")
      (fields (field (name "PUBLISHER") "Altium Limited"))
      (libsource (lib "Panasonic Resistor") (part "ERA6Y"))
    )
    (comp (ref "R66")
      (value "10K")
      (footprint "ERA-0805")
      (fields (field (name "PUBLISHER") "Altium Limited"))
      (libsource (lib "Panasonic Resistor") (part "ERA6Y"))
    )
    (comp (ref "R67")
      (value "1K")
      (footprint "ERA-0805")
      (fields (field (name "PUBLISHER") "Altium Limited"))
      (libsource (lib "Panasonic Resistor") (part "ERA6Y"))
    )
    (comp (ref "R68")
      (value "1K")
      (footprint "ERA-0805")
      (fields (field (name "PUBLISHER") "Altium Limited"))
      (libsource (lib "Panasonic Resistor") (part "ERA6Y"))
    )
    (comp (ref "R69")
      (value "1K")
      (footprint "ERA-0805")
      (fields (field (name "PUBLISHER") "Altium Limited"))
      (libsource (lib "Panasonic Resistor") (part "ERA6Y"))
    )
    (comp (ref "R70")
      (value "1K")
      (footprint "ERA-0805")
      (fields (field (name "PUBLISHER") "Altium Limited"))
      (libsource (lib "Panasonic Resistor") (part "ERA6Y"))
    )
    (comp (ref "R71")
      (value "10K")
      (footprint "12-1812")
      (description "Thick Film Chip Resistor, 1 Ohm to 10M Ohm Range, 5% Tolerance, 1812 Size, 0.5 W")
      (fields (field (name "PUBLISHER") "Altium Limited"))
      (libsource (lib "Panasonic Resistor") (part "ERJ12"))
    )
    (comp (ref "R72")
      (value "10K")
      (footprint "12-1812")
      (description "Thick Film Chip Resistor, 1 Ohm to 10M Ohm Range, 5% Tolerance, 1812 Size, 0.5 W")
      (fields (field (name "PUBLISHER") "Altium Limited"))
      (libsource (lib "Panasonic Resistor") (part "ERJ12"))
    )
    (comp (ref "R73")
      (value "10K")
      (footprint "12-1812")
      (description "Thick Film Chip Resistor, 1 Ohm to 10M Ohm Range, 5% Tolerance, 1812 Size, 0.5 W")
      (fields (field (name "PUBLISHER") "Altium Limited"))
      (libsource (lib "Panasonic Resistor") (part "ERJ12"))
    )
    (comp (ref "R74")
      (value "10K")
      (footprint "12-1812")
      (description "Thick Film Chip Resistor, 1 Ohm to 10M Ohm Range, 5% Tolerance, 1812 Size, 0.5 W")
      (fields (field (name "PUBLISHER") "Altium Limited"))
      (libsource (lib "Panasonic Resistor") (part "ERJ12"))
    )
    (comp (ref "R75")
      (value "1K")
      (footprint "ERA-0805")
      (fields (field (name "PUBLISHER") "Altium Limited"))
      (libsource (lib "Panasonic Resistor") (part "ERA6Y"))
    )
    (comp (ref "R76")
      (value "100R")
      (footprint "ERA-0805")
      (fields (field (name "PUBLISHER") "Altium Limited"))
      (libsource (lib "Panasonic Resistor") (part "ERA6Y"))
    )
    (comp (ref "R77")
      (value "1K")
      (footprint "ERA-0805")
      (fields (field (name "PUBLISHER") "Altium Limited"))
      (libsource (lib "Panasonic Resistor") (part "ERA6Y"))
    )
    (comp (ref "R78")
      (value "100R")
      (footprint "ERA-0805")
      (fields (field (name "PUBLISHER") "Altium Limited"))
      (libsource (lib "Panasonic Resistor") (part "ERA6Y"))
    )
    (comp (ref "R79")
      (value "100R")
      (footprint "ERA-0805")
      (fields (field (name "PUBLISHER") "Altium Limited"))
      (libsource (lib "Panasonic Resistor") (part "ERA6Y"))
    )
    (comp (ref "R80")
      (value "100R")
      (footprint "ERA-0805")
      (fields (field (name "PUBLISHER") "Altium Limited"))
      (libsource (lib "Panasonic Resistor") (part "ERA6Y"))
    )
    (comp (ref "R81")
      (value "1K")
      (footprint "ERA-0805")
      (fields (field (name "PUBLISHER") "Altium Limited"))
      (libsource (lib "Panasonic Resistor") (part "ERA6Y"))
    )
    (comp (ref "R82")
      (value "100R")
      (footprint "ERA-0805")
      (fields (field (name "PUBLISHER") "Altium Limited"))
      (libsource (lib "Panasonic Resistor") (part "ERA6Y"))
    )
    (comp (ref "R83")
      (value "1K")
      (footprint "ERA-0805")
      (fields (field (name "PUBLISHER") "Altium Limited"))
      (libsource (lib "Panasonic Resistor") (part "ERA6Y"))
    )
    (comp (ref "R84")
      (value "100R")
      (footprint "ERA-0805")
      (fields (field (name "PUBLISHER") "Altium Limited"))
      (libsource (lib "Panasonic Resistor") (part "ERA6Y"))
    )
    (comp (ref "R85")
      (value "100R")
      (footprint "ERA-0805")
      (fields (field (name "PUBLISHER") "Altium Limited"))
      (libsource (lib "Panasonic Resistor") (part "ERA6Y"))
    )
    (comp (ref "R86")
      (value "100R")
      (footprint "ERA-0805")
      (fields (field (name "PUBLISHER") "Altium Limited"))
      (libsource (lib "Panasonic Resistor") (part "ERA6Y"))
    )
    (comp (ref "R87")
      (value "10K")
      (footprint "ERA-0805")
      (fields (field (name "PUBLISHER") "Altium Limited"))
      (libsource (lib "Panasonic Resistor") (part "ERA6Y"))
    )
    (comp (ref "R88")
      (value "10K")
      (footprint "ERA-0805")
      (fields (field (name "PUBLISHER") "Altium Limited"))
      (libsource (lib "Panasonic Resistor") (part "ERA6Y"))
    )
    (comp (ref "R89")
      (value "10K")
      (footprint "ERA-0805")
      (fields (field (name "PUBLISHER") "Altium Limited"))
      (libsource (lib "Panasonic Resistor") (part "ERA6Y"))
    )
    (comp (ref "R90")
      (value "10K")
      (footprint "ERA-0805")
      (fields (field (name "PUBLISHER") "Altium Limited"))
      (libsource (lib "Panasonic Resistor") (part "ERA6Y"))
    )
    (comp (ref "R91")
      (value "1K")
      (footprint "ERA-0805")
      (fields (field (name "PUBLISHER") "Altium Limited"))
      (libsource (lib "Panasonic Resistor") (part "ERA6Y"))
    )
    (comp (ref "R92")
      (value "1K")
      (footprint "ERA-0805")
      (fields (field (name "PUBLISHER") "Altium Limited"))
      (libsource (lib "Panasonic Resistor") (part "ERA6Y"))
    )
    (comp (ref "R93")
      (value "1K")
      (footprint "ERA-0805")
      (fields (field (name "PUBLISHER") "Altium Limited"))
      (libsource (lib "Panasonic Resistor") (part "ERA6Y"))
    )
    (comp (ref "R94")
      (value "1K")
      (footprint "ERA-0805")
      (fields (field (name "PUBLISHER") "Altium Limited"))
      (libsource (lib "Panasonic Resistor") (part "ERA6Y"))
    )
    (comp (ref "R95")
      (value "10K")
      (footprint "12-1812")
      (description "Thick Film Chip Resistor, 1 Ohm to 10M Ohm Range, 5% Tolerance, 1812 Size, 0.5 W")
      (fields (field (name "PUBLISHER") "Altium Limited"))
      (libsource (lib "Panasonic Resistor") (part "ERJ12"))
    )
    (comp (ref "R96")
      (value "10K")
      (footprint "12-1812")
      (description "Thick Film Chip Resistor, 1 Ohm to 10M Ohm Range, 5% Tolerance, 1812 Size, 0.5 W")
      (fields (field (name "PUBLISHER") "Altium Limited"))
      (libsource (lib "Panasonic Resistor") (part "ERJ12"))
    )
    (comp (ref "R97")
      (value "10K")
      (footprint "12-1812")
      (description "Thick Film Chip Resistor, 1 Ohm to 10M Ohm Range, 5% Tolerance, 1812 Size, 0.5 W")
      (fields (field (name "PUBLISHER") "Altium Limited"))
      (libsource (lib "Panasonic Resistor") (part "ERJ12"))
    )
    (comp (ref "R98")
      (value "10K")
      (footprint "12-1812")
      (description "Thick Film Chip Resistor, 1 Ohm to 10M Ohm Range, 5% Tolerance, 1812 Size, 0.5 W")
      (fields (field (name "PUBLISHER") "Altium Limited"))
      (libsource (lib "Panasonic Resistor") (part "ERJ12"))
    )
    (comp (ref "R99")
      (value "1K")
      (footprint "ERA-0805")
      (fields (field (name "PUBLISHER") "Altium Limited"))
      (libsource (lib "Panasonic Resistor") (part "ERA6Y"))
    )
    (comp (ref "R100")
      (value "100R")
      (footprint "ERA-0805")
      (fields (field (name "PUBLISHER") "Altium Limited"))
      (libsource (lib "Panasonic Resistor") (part "ERA6Y"))
    )
    (comp (ref "R101")
      (value "1K")
      (footprint "ERA-0805")
      (fields (field (name "PUBLISHER") "Altium Limited"))
      (libsource (lib "Panasonic Resistor") (part "ERA6Y"))
    )
    (comp (ref "R102")
      (value "100R")
      (footprint "ERA-0805")
      (fields (field (name "PUBLISHER") "Altium Limited"))
      (libsource (lib "Panasonic Resistor") (part "ERA6Y"))
    )
    (comp (ref "R103")
      (value "100R")
      (footprint "ERA-0805")
      (fields (field (name "PUBLISHER") "Altium Limited"))
      (libsource (lib "Panasonic Resistor") (part "ERA6Y"))
    )
    (comp (ref "R104")
      (value "100R")
      (footprint "ERA-0805")
      (fields (field (name "PUBLISHER") "Altium Limited"))
      (libsource (lib "Panasonic Resistor") (part "ERA6Y"))
    )
    (comp (ref "R105")
      (value "1K")
      (footprint "ERA-0805")
      (fields (field (name "PUBLISHER") "Altium Limited"))
      (libsource (lib "Panasonic Resistor") (part "ERA6Y"))
    )
    (comp (ref "R106")
      (value "100R")
      (footprint "ERA-0805")
      (fields (field (name "PUBLISHER") "Altium Limited"))
      (libsource (lib "Panasonic Resistor") (part "ERA6Y"))
    )
    (comp (ref "R107")
      (value "1K")
      (footprint "ERA-0805")
      (fields (field (name "PUBLISHER") "Altium Limited"))
      (libsource (lib "Panasonic Resistor") (part "ERA6Y"))
    )
    (comp (ref "R108")
      (value "100R")
      (footprint "ERA-0805")
      (fields (field (name "PUBLISHER") "Altium Limited"))
      (libsource (lib "Panasonic Resistor") (part "ERA6Y"))
    )
    (comp (ref "R109")
      (value "100R")
      (footprint "ERA-0805")
      (fields (field (name "PUBLISHER") "Altium Limited"))
      (libsource (lib "Panasonic Resistor") (part "ERA6Y"))
    )
    (comp (ref "R110")
      (value "100R")
      (footprint "ERA-0805")
      (fields (field (name "PUBLISHER") "Altium Limited"))
      (libsource (lib "Panasonic Resistor") (part "ERA6Y"))
    )
    (comp (ref "R111")
      (value "10K")
      (footprint "ERA-0805")
      (fields (field (name "PUBLISHER") "Altium Limited"))
      (libsource (lib "Panasonic Resistor") (part "ERA6Y"))
    )
    (comp (ref "R112")
      (value "10K")
      (footprint "ERA-0805")
      (fields (field (name "PUBLISHER") "Altium Limited"))
      (libsource (lib "Panasonic Resistor") (part "ERA6Y"))
    )
    (comp (ref "R113")
      (value "10K")
      (footprint "ERA-0805")
      (fields (field (name "PUBLISHER") "Altium Limited"))
      (libsource (lib "Panasonic Resistor") (part "ERA6Y"))
    )
    (comp (ref "R114")
      (value "10K")
      (footprint "ERA-0805")
      (fields (field (name "PUBLISHER") "Altium Limited"))
      (libsource (lib "Panasonic Resistor") (part "ERA6Y"))
    )
    (comp (ref "R115")
      (value "1K")
      (footprint "ERA-0805")
      (fields (field (name "PUBLISHER") "Altium Limited"))
      (libsource (lib "Panasonic Resistor") (part "ERA6Y"))
    )
    (comp (ref "R116")
      (value "1K")
      (footprint "ERA-0805")
      (fields (field (name "PUBLISHER") "Altium Limited"))
      (libsource (lib "Panasonic Resistor") (part "ERA6Y"))
    )
    (comp (ref "R117")
      (value "1K")
      (footprint "ERA-0805")
      (fields (field (name "PUBLISHER") "Altium Limited"))
      (libsource (lib "Panasonic Resistor") (part "ERA6Y"))
    )
    (comp (ref "R118")
      (value "1K")
      (footprint "ERA-0805")
      (fields (field (name "PUBLISHER") "Altium Limited"))
      (libsource (lib "Panasonic Resistor") (part "ERA6Y"))
    )
    (comp (ref "R119")
      (value "10K")
      (footprint "12-1812")
      (description "Thick Film Chip Resistor, 1 Ohm to 10M Ohm Range, 5% Tolerance, 1812 Size, 0.5 W")
      (fields (field (name "PUBLISHER") "Altium Limited"))
      (libsource (lib "Panasonic Resistor") (part "ERJ12"))
    )
    (comp (ref "R120")
      (value "10K")
      (footprint "12-1812")
      (description "Thick Film Chip Resistor, 1 Ohm to 10M Ohm Range, 5% Tolerance, 1812 Size, 0.5 W")
      (fields (field (name "PUBLISHER") "Altium Limited"))
      (libsource (lib "Panasonic Resistor") (part "ERJ12"))
    )
    (comp (ref "R121")
      (value "10K")
      (footprint "12-1812")
      (description "Thick Film Chip Resistor, 1 Ohm to 10M Ohm Range, 5% Tolerance, 1812 Size, 0.5 W")
      (fields (field (name "PUBLISHER") "Altium Limited"))
      (libsource (lib "Panasonic Resistor") (part "ERJ12"))
    )
    (comp (ref "R122")
      (value "10K")
      (footprint "12-1812")
      (description "Thick Film Chip Resistor, 1 Ohm to 10M Ohm Range, 5% Tolerance, 1812 Size, 0.5 W")
      (fields (field (name "PUBLISHER") "Altium Limited"))
      (libsource (lib "Panasonic Resistor") (part "ERJ12"))
    )
    (comp (ref "R123")
      (value "1K")
      (footprint "ERA-0805")
      (fields (field (name "PUBLISHER") "Altium Limited"))
      (libsource (lib "Panasonic Resistor") (part "ERA6Y"))
    )
    (comp (ref "R124")
      (value "100R")
      (footprint "ERA-0805")
      (fields (field (name "PUBLISHER") "Altium Limited"))
      (libsource (lib "Panasonic Resistor") (part "ERA6Y"))
    )
    (comp (ref "R125")
      (value "1K")
      (footprint "ERA-0805")
      (fields (field (name "PUBLISHER") "Altium Limited"))
      (libsource (lib "Panasonic Resistor") (part "ERA6Y"))
    )
    (comp (ref "R126")
      (value "100R")
      (footprint "ERA-0805")
      (fields (field (name "PUBLISHER") "Altium Limited"))
      (libsource (lib "Panasonic Resistor") (part "ERA6Y"))
    )
    (comp (ref "R127")
      (value "100R")
      (footprint "ERA-0805")
      (fields (field (name "PUBLISHER") "Altium Limited"))
      (libsource (lib "Panasonic Resistor") (part "ERA6Y"))
    )
    (comp (ref "R128")
      (value "100R")
      (footprint "ERA-0805")
      (fields (field (name "PUBLISHER") "Altium Limited"))
      (libsource (lib "Panasonic Resistor") (part "ERA6Y"))
    )
    (comp (ref "R129")
      (value "1K")
      (footprint "ERA-0805")
      (fields (field (name "PUBLISHER") "Altium Limited"))
      (libsource (lib "Panasonic Resistor") (part "ERA6Y"))
    )
    (comp (ref "R130")
      (value "100R")
      (footprint "ERA-0805")
      (fields (field (name "PUBLISHER") "Altium Limited"))
      (libsource (lib "Panasonic Resistor") (part "ERA6Y"))
    )
    (comp (ref "R131")
      (value "1K")
      (footprint "ERA-0805")
      (fields (field (name "PUBLISHER") "Altium Limited"))
      (libsource (lib "Panasonic Resistor") (part "ERA6Y"))
    )
    (comp (ref "R132")
      (value "100R")
      (footprint "ERA-0805")
      (fields (field (name "PUBLISHER") "Altium Limited"))
      (libsource (lib "Panasonic Resistor") (part "ERA6Y"))
    )
    (comp (ref "R133")
      (value "100R")
      (footprint "ERA-0805")
      (fields (field (name "PUBLISHER") "Altium Limited"))
      (libsource (lib "Panasonic Resistor") (part "ERA6Y"))
    )
    (comp (ref "R134")
      (value "100R")
      (footprint "ERA-0805")
      (fields (field (name "PUBLISHER") "Altium Limited"))
      (libsource (lib "Panasonic Resistor") (part "ERA6Y"))
    )
    (comp (ref "R135")
      (value "10K")
      (footprint "ERA-0805")
      (fields (field (name "PUBLISHER") "Altium Limited"))
      (libsource (lib "Panasonic Resistor") (part "ERA6Y"))
    )
    (comp (ref "R136")
      (value "10K")
      (footprint "ERA-0805")
      (fields (field (name "PUBLISHER") "Altium Limited"))
      (libsource (lib "Panasonic Resistor") (part "ERA6Y"))
    )
    (comp (ref "R137")
      (value "10K")
      (footprint "ERA-0805")
      (fields (field (name "PUBLISHER") "Altium Limited"))
      (libsource (lib "Panasonic Resistor") (part "ERA6Y"))
    )
    (comp (ref "R138")
      (value "10K")
      (footprint "ERA-0805")
      (fields (field (name "PUBLISHER") "Altium Limited"))
      (libsource (lib "Panasonic Resistor") (part "ERA6Y"))
    )
    (comp (ref "R139")
      (value "1K")
      (footprint "ERA-0805")
      (fields (field (name "PUBLISHER") "Altium Limited"))
      (libsource (lib "Panasonic Resistor") (part "ERA6Y"))
    )
    (comp (ref "R140")
      (value "1K")
      (footprint "ERA-0805")
      (fields (field (name "PUBLISHER") "Altium Limited"))
      (libsource (lib "Panasonic Resistor") (part "ERA6Y"))
    )
    (comp (ref "R141")
      (value "1K")
      (footprint "ERA-0805")
      (fields (field (name "PUBLISHER") "Altium Limited"))
      (libsource (lib "Panasonic Resistor") (part "ERA6Y"))
    )
    (comp (ref "R142")
      (value "1K")
      (footprint "ERA-0805")
      (fields (field (name "PUBLISHER") "Altium Limited"))
      (libsource (lib "Panasonic Resistor") (part "ERA6Y"))
    )
    (comp (ref "U16")
      (value "STEP DOWN BUCK")
      (footprint "TO220")
      (description "Positive Voltage Regulator, 5V, 3-Pin TO-220")
      (fields (field (name "PARTNUMBER") "L7805CV"))
      (libsource (lib "sch_library") (part "L7805CV"))
    )
    (comp (ref "U17")
      (value "B0512S/D-1W")
      (footprint "B0505S-1W")
      (description "1W isolated dc dc converter")
      (libsource (lib "DE-130817") (part "B0505S/D"))
    )
    (comp (ref "U18")
      (value "B0512S/D-1W")
      (footprint "B0505S-1W")
      (description "1W isolated dc dc converter")
      (libsource (lib "DE-130817") (part "B0505S/D"))
    )
  )
  (nets
    (net (code "1") (name "+5V_P") (class "Default")
      (node (ref "C52") (pin "1") (pinfunction "1_1") (pintype "passive"))
      (node (ref "C52") (pin "2") (pinfunction "2_2") (pintype "passive"))
      (node (ref "C53") (pin "1") (pinfunction "1_1") (pintype "passive"))
      (node (ref "C53") (pin "2") (pinfunction "2_2") (pintype "passive"))
      (node (ref "C54") (pin "1") (pinfunction "1_1") (pintype "passive"))
      (node (ref "C54") (pin "2") (pinfunction "2_2") (pintype "passive"))
      (node (ref "C55") (pin "1") (pinfunction "1_1") (pintype "passive"))
      (node (ref "C58") (pin "1") (pinfunction "1_1") (pintype "passive"))
      (node (ref "C58") (pin "2") (pinfunction "2_2") (pintype "passive"))
      (node (ref "C59") (pin "1") (pinfunction "1_1") (pintype "passive"))
      (node (ref "C59") (pin "2") (pinfunction "2_2") (pintype "passive"))
      (node (ref "C60") (pin "1") (pinfunction "1_1") (pintype "passive"))
      (node (ref "C60") (pin "2") (pinfunction "2_2") (pintype "passive"))
      (node (ref "C79") (pin "2") (pinfunction "2_2") (pintype "passive"))
      (node (ref "C80") (pin "2") (pinfunction "2_2") (pintype "passive"))
      (node (ref "C81") (pin "1") (pinfunction "1_1") (pintype "passive"))
      (node (ref "C82") (pin "1") (pinfunction "1_1") (pintype "passive"))
      (node (ref "C82") (pin "2") (pinfunction "2_2") (pintype "passive"))
      (node (ref "P30") (pin "2") (pinfunction "2_2") (pintype "passive"))
      (node (ref "P31") (pin "2") (pinfunction "2_2") (pintype "passive"))
      (node (ref "P32") (pin "2") (pinfunction "2_2") (pintype "passive"))
      (node (ref "P33") (pin "2") (pinfunction "2_2") (pintype "passive"))
      (node (ref "P34") (pin "2") (pinfunction "2_2") (pintype "passive"))
      (node (ref "P35") (pin "2") (pinfunction "2_2") (pintype "passive"))
      (node (ref "P36") (pin "2") (pinfunction "2_2") (pintype "passive"))
      (node (ref "P37") (pin "2") (pinfunction "2_2") (pintype "passive"))
      (node (ref "P38") (pin "2") (pinfunction "2_2") (pintype "passive"))
      (node (ref "P39") (pin "2") (pinfunction "2_2") (pintype "passive"))
      (node (ref "P40") (pin "2") (pinfunction "2_2") (pintype "passive"))
      (node (ref "P41") (pin "2") (pinfunction "2_2") (pintype "passive"))
      (node (ref "P42") (pin "2") (pinfunction "2_2") (pintype "passive"))
      (node (ref "P43") (pin "2") (pinfunction "2_2") (pintype "passive"))
      (node (ref "P44") (pin "2") (pinfunction "2_2") (pintype "passive"))
      (node (ref "P45") (pin "2") (pinfunction "2_2") (pintype "passive"))
      (node (ref "P46") (pin "2") (pinfunction "2_2") (pintype "passive"))
      (node (ref "P47") (pin "17") (pinfunction "17_17") (pintype "passive"))
      (node (ref "P47") (pin "18") (pinfunction "18_18") (pintype "passive"))
      (node (ref "Q10") (pin "2") (pinfunction "E_2") (pintype "passive"))
      (node (ref "Q12") (pin "2") (pinfunction "E_2") (pintype "passive"))
      (node (ref "Q14") (pin "2") (pinfunction "E_2") (pintype "passive"))
      (node (ref "Q16") (pin "3") (pinfunction "C_3") (pintype "passive"))
      (node (ref "Q17") (pin "3") (pinfunction "C_3") (pintype "passive"))
      (node (ref "Q18") (pin "2") (pinfunction "S_2") (pintype "passive"))
      (node (ref "Q19") (pin "2") (pinfunction "S_2") (pintype "passive"))
      (node (ref "Q20") (pin "2") (pinfunction "S_2") (pintype "passive"))
      (node (ref "Q21") (pin "2") (pinfunction "S_2") (pintype "passive"))
      (node (ref "Q22") (pin "3") (pinfunction "C_3") (pintype "passive"))
      (node (ref "Q23") (pin "3") (pinfunction "C_3") (pintype "passive"))
      (node (ref "Q28") (pin "2") (pinfunction "E_2") (pintype "passive"))
      (node (ref "Q30") (pin "2") (pinfunction "E_2") (pintype "passive"))
      (node (ref "Q32") (pin "2") (pinfunction "E_2") (pintype "passive"))
      (node (ref "Q34") (pin "2") (pinfunction "E_2") (pintype "passive"))
      (node (ref "Q36") (pin "2") (pinfunction "S_2") (pintype "passive"))
      (node (ref "Q37") (pin "2") (pinfunction "S_2") (pintype "passive"))
      (node (ref "Q38") (pin "2") (pinfunction "S_2") (pintype "passive"))
      (node (ref "Q39") (pin "2") (pinfunction "S_2") (pintype "passive"))
      (node (ref "Q40") (pin "3") (pinfunction "C_3") (pintype "passive"))
      (node (ref "Q41") (pin "3") (pinfunction "C_3") (pintype "passive"))
      (node (ref "Q42") (pin "3") (pinfunction "C_3") (pintype "passive"))
      (node (ref "Q43") (pin "3") (pinfunction "C_3") (pintype "passive"))
      (node (ref "Q48") (pin "2") (pinfunction "E_2") (pintype "passive"))
      (node (ref "Q50") (pin "2") (pinfunction "E_2") (pintype "passive"))
      (node (ref "Q52") (pin "2") (pinfunction "E_2") (pintype "passive"))
      (node (ref "Q54") (pin "2") (pinfunction "E_2") (pintype "passive"))
      (node (ref "Q56") (pin "2") (pinfunction "S_2") (pintype "passive"))
      (node (ref "Q57") (pin "2") (pinfunction "S_2") (pintype "passive"))
      (node (ref "Q58") (pin "2") (pinfunction "S_2") (pintype "passive"))
      (node (ref "Q59") (pin "2") (pinfunction "S_2") (pintype "passive"))
      (node (ref "Q60") (pin "3") (pinfunction "C_3") (pintype "passive"))
      (node (ref "Q61") (pin "3") (pinfunction "C_3") (pintype "passive"))
      (node (ref "Q62") (pin "3") (pinfunction "C_3") (pintype "passive"))
      (node (ref "Q63") (pin "3") (pinfunction "C_3") (pintype "passive"))
      (node (ref "Q68") (pin "2") (pinfunction "E_2") (pintype "passive"))
      (node (ref "Q70") (pin "2") (pinfunction "E_2") (pintype "passive"))
      (node (ref "Q72") (pin "2") (pinfunction "E_2") (pintype "passive"))
      (node (ref "Q74") (pin "2") (pinfunction "E_2") (pintype "passive"))
      (node (ref "Q76") (pin "2") (pinfunction "S_2") (pintype "passive"))
      (node (ref "Q77") (pin "2") (pinfunction "S_2") (pintype "passive"))
      (node (ref "Q78") (pin "2") (pinfunction "S_2") (pintype "passive"))
      (node (ref "Q79") (pin "2") (pinfunction "S_2") (pintype "passive"))
      (node (ref "Q8") (pin "2") (pinfunction "E_2") (pintype "passive"))
      (node (ref "Q80") (pin "3") (pinfunction "C_3") (pintype "passive"))
      (node (ref "Q81") (pin "3") (pinfunction "C_3") (pintype "passive"))
      (node (ref "Q82") (pin "3") (pinfunction "C_3") (pintype "passive"))
      (node (ref "Q83") (pin "3") (pinfunction "C_3") (pintype "passive"))
      (node (ref "R111") (pin "1") (pinfunction "1_1") (pintype "passive"))
      (node (ref "R112") (pin "1") (pinfunction "1_1") (pintype "passive"))
      (node (ref "R113") (pin "1") (pinfunction "1_1") (pintype "passive"))
      (node (ref "R114") (pin "1") (pinfunction "1_1") (pintype "passive"))
      (node (ref "R115") (pin "2") (pinfunction "2_2") (pintype "passive"))
      (node (ref "R116") (pin "2") (pinfunction "2_2") (pintype "passive"))
      (node (ref "R117") (pin "2") (pinfunction "2_2") (pintype "passive"))
      (node (ref "R118") (pin "2") (pinfunction "2_2") (pintype "passive"))
      (node (ref "R135") (pin "1") (pinfunction "1_1") (pintype "passive"))
      (node (ref "R136") (pin "1") (pinfunction "1_1") (pintype "passive"))
      (node (ref "R137") (pin "1") (pinfunction "1_1") (pintype "passive"))
      (node (ref "R138") (pin "1") (pinfunction "1_1") (pintype "passive"))
      (node (ref "R139") (pin "2") (pinfunction "2_2") (pintype "passive"))
      (node (ref "R140") (pin "2") (pinfunction "2_2") (pintype "passive"))
      (node (ref "R141") (pin "2") (pinfunction "2_2") (pintype "passive"))
      (node (ref "R142") (pin "2") (pinfunction "2_2") (pintype "passive"))
      (node (ref "R63") (pin "1") (pinfunction "1_1") (pintype "passive"))
      (node (ref "R64") (pin "1") (pinfunction "1_1") (pintype "passive"))
      (node (ref "R65") (pin "1") (pinfunction "1_1") (pintype "passive"))
      (node (ref "R66") (pin "1") (pinfunction "1_1") (pintype "passive"))
      (node (ref "R67") (pin "2") (pinfunction "2_2") (pintype "passive"))
      (node (ref "R68") (pin "2") (pinfunction "2_2") (pintype "passive"))
      (node (ref "R69") (pin "2") (pinfunction "2_2") (pintype "passive"))
      (node (ref "R70") (pin "2") (pinfunction "2_2") (pintype "passive"))
      (node (ref "R87") (pin "1") (pinfunction "1_1") (pintype "passive"))
      (node (ref "R88") (pin "1") (pinfunction "1_1") (pintype "passive"))
      (node (ref "R89") (pin "1") (pinfunction "1_1") (pintype "passive"))
      (node (ref "R90") (pin "1") (pinfunction "1_1") (pintype "passive"))
      (node (ref "R91") (pin "2") (pinfunction "2_2") (pintype "passive"))
      (node (ref "R92") (pin "2") (pinfunction "2_2") (pintype "passive"))
      (node (ref "R93") (pin "2") (pinfunction "2_2") (pintype "passive"))
      (node (ref "R94") (pin "2") (pinfunction "2_2") (pintype "passive"))
      (node (ref "U16") (pin "2") (pinfunction "GND_2") (pintype "power_in"))
      (node (ref "U16") (pin "3") (pinfunction "OUT_3") (pintype "power_in"))
      (node (ref "U17") (pin "1") (pinfunction "GND_1") (pintype "passive"))
      (node (ref "U17") (pin "2") (pinfunction "+Vin_2") (pintype "passive"))
      (node (ref "U18") (pin "1") (pinfunction "GND_1") (pintype "passive"))
      (node (ref "U18") (pin "2") (pinfunction "+Vin_2") (pintype "passive"))
    )
    (net (code "2") (name "+BAT_PWM") (class "Default")
      (node (ref "C55") (pin "2") (pinfunction "2_2") (pintype "passive"))
      (node (ref "C56") (pin "2") (pinfunction "2_2") (pintype "passive"))
      (node (ref "C57") (pin "1") (pinfunction "1_1") (pintype "passive"))
      (node (ref "C61") (pin "1") (pinfunction "1_1") (pintype "passive"))
      (node (ref "C62") (pin "1") (pinfunction "1_1") (pintype "passive"))
      (node (ref "C79") (pin "1") (pinfunction "1_1") (pintype "passive"))
      (node (ref "C80") (pin "1") (pinfunction "1_1") (pintype "passive"))
      (node (ref "C81") (pin "2") (pinfunction "2_2") (pintype "passive"))
      (node (ref "C83") (pin "1") (pinfunction "1_1") (pintype "passive"))
      (node (ref "P38") (pin "1") (pinfunction "1_1") (pintype "passive"))
      (node (ref "Q11") (pin "2") (pinfunction "D_2") (pintype "passive"))
      (node (ref "Q13") (pin "2") (pinfunction "D_2") (pintype "passive"))
      (node (ref "Q15") (pin "2") (pinfunction "D_2") (pintype "passive"))
      (node (ref "Q29") (pin "2") (pinfunction "D_2") (pintype "passive"))
      (node (ref "Q31") (pin "2") (pinfunction "D_2") (pintype "passive"))
      (node (ref "Q33") (pin "2") (pinfunction "D_2") (pintype "passive"))
      (node (ref "Q35") (pin "2") (pinfunction "D_2") (pintype "passive"))
      (node (ref "Q49") (pin "2") (pinfunction "D_2") (pintype "passive"))
      (node (ref "Q51") (pin "2") (pinfunction "D_2") (pintype "passive"))
      (node (ref "Q53") (pin "2") (pinfunction "D_2") (pintype "passive"))
      (node (ref "Q55") (pin "2") (pinfunction "D_2") (pintype "passive"))
      (node (ref "Q69") (pin "2") (pinfunction "D_2") (pintype "passive"))
      (node (ref "Q71") (pin "2") (pinfunction "D_2") (pintype "passive"))
      (node (ref "Q73") (pin "2") (pinfunction "D_2") (pintype "passive"))
      (node (ref "Q75") (pin "2") (pinfunction "D_2") (pintype "passive"))
      (node (ref "Q9") (pin "2") (pinfunction "D_2") (pintype "passive"))
      (node (ref "U16") (pin "1") (pinfunction "IN_1") (pintype "power_in"))
      (node (ref "U17") (pin "3") (pinfunction "0V_3") (pintype "passive"))
      (node (ref "U18") (pin "3") (pinfunction "0V_3") (pintype "passive"))
    )
    (net (code "3") (name "/PWM_0") (class "Default")
      (node (ref "P47") (pin "1") (pinfunction "1_1") (pintype "passive"))
      (node (ref "R51") (pin "1") (pinfunction "1_1") (pintype "passive"))
      (node (ref "R63") (pin "2") (pinfunction "2_2") (pintype "passive"))
    )
    (net (code "4") (name "/PWM_0_OUT") (class "Default")
      (node (ref "D13") (pin "2") (pinfunction "A_2") (pintype "passive"))
      (node (ref "P30") (pin "1") (pinfunction "1_1") (pintype "passive"))
      (node (ref "Q9") (pin "3") (pinfunction "S_3") (pintype "passive"))
    )
    (net (code "5") (name "/PWM_1") (class "Default")
      (node (ref "P47") (pin "2") (pinfunction "2_2") (pintype "passive"))
      (node (ref "R53") (pin "1") (pinfunction "1_1") (pintype "passive"))
      (node (ref "R64") (pin "2") (pinfunction "2_2") (pintype "passive"))
    )
    (net (code "6") (name "/PWM_1_OUT") (class "Default")
      (node (ref "D14") (pin "2") (pinfunction "A_2") (pintype "passive"))
      (node (ref "P31") (pin "1") (pinfunction "1_1") (pintype "passive"))
      (node (ref "Q11") (pin "3") (pinfunction "S_3") (pintype "passive"))
    )
    (net (code "7") (name "/PWM_2") (class "Default")
      (node (ref "P47") (pin "3") (pinfunction "3_3") (pintype "passive"))
      (node (ref "R57") (pin "1") (pinfunction "1_1") (pintype "passive"))
      (node (ref "R65") (pin "2") (pinfunction "2_2") (pintype "passive"))
    )
    (net (code "8") (name "/PWM_2_OUT") (class "Default")
      (node (ref "D15") (pin "2") (pinfunction "A_2") (pintype "passive"))
      (node (ref "P32") (pin "1") (pinfunction "1_1") (pintype "passive"))
      (node (ref "Q13") (pin "3") (pinfunction "S_3") (pintype "passive"))
    )
    (net (code "9") (name "/PWM_3") (class "Default")
      (node (ref "P47") (pin "4") (pinfunction "4_4") (pintype "passive"))
      (node (ref "R59") (pin "1") (pinfunction "1_1") (pintype "passive"))
      (node (ref "R66") (pin "2") (pinfunction "2_2") (pintype "passive"))
    )
    (net (code "10") (name "/PWM_3_OUT") (class "Default")
      (node (ref "D16") (pin "2") (pinfunction "A_2") (pintype "passive"))
      (node (ref "P33") (pin "1") (pinfunction "1_1") (pintype "passive"))
      (node (ref "Q15") (pin "3") (pinfunction "S_3") (pintype "passive"))
    )
    (net (code "11") (name "/PWM_4") (class "Default")
      (node (ref "P47") (pin "5") (pinfunction "5_5") (pintype "passive"))
      (node (ref "R75") (pin "1") (pinfunction "1_1") (pintype "passive"))
      (node (ref "R87") (pin "2") (pinfunction "2_2") (pintype "passive"))
    )
    (net (code "12") (name "/PWM_4_OUT") (class "Default")
      (node (ref "D17") (pin "2") (pinfunction "A_2") (pintype "passive"))
      (node (ref "P34") (pin "1") (pinfunction "1_1") (pintype "passive"))
      (node (ref "Q29") (pin "3") (pinfunction "S_3") (pintype "passive"))
    )
    (net (code "13") (name "/PWM_5") (class "Default")
      (node (ref "P47") (pin "6") (pinfunction "6_6") (pintype "passive"))
      (node (ref "R77") (pin "1") (pinfunction "1_1") (pintype "passive"))
      (node (ref "R88") (pin "2") (pinfunction "2_2") (pintype "passive"))
    )
    (net (code "14") (name "/PWM_5_OUT") (class "Default")
      (node (ref "D18") (pin "2") (pinfunction "A_2") (pintype "passive"))
      (node (ref "P35") (pin "1") (pinfunction "1_1") (pintype "passive"))
      (node (ref "Q31") (pin "3") (pinfunction "S_3") (pintype "passive"))
    )
    (net (code "15") (name "/PWM_6") (class "Default")
      (node (ref "P47") (pin "7") (pinfunction "7_7") (pintype "passive"))
      (node (ref "R81") (pin "1") (pinfunction "1_1") (pintype "passive"))
      (node (ref "R89") (pin "2") (pinfunction "2_2") (pintype "passive"))
    )
    (net (code "16") (name "/PWM_6_OUT") (class "Default")
      (node (ref "D19") (pin "2") (pinfunction "A_2") (pintype "passive"))
      (node (ref "P36") (pin "1") (pinfunction "1_1") (pintype "passive"))
      (node (ref "Q33") (pin "3") (pinfunction "S_3") (pintype "passive"))
    )
    (net (code "17") (name "/PWM_7") (class "Default")
      (node (ref "P47") (pin "8") (pinfunction "8_8") (pintype "passive"))
      (node (ref "R83") (pin "1") (pinfunction "1_1") (pintype "passive"))
      (node (ref "R90") (pin "2") (pinfunction "2_2") (pintype "passive"))
    )
    (net (code "18") (name "/PWM_7_OUT") (class "Default")
      (node (ref "D20") (pin "2") (pinfunction "A_2") (pintype "passive"))
      (node (ref "P37") (pin "1") (pinfunction "1_1") (pintype "passive"))
      (node (ref "Q35") (pin "3") (pinfunction "S_3") (pintype "passive"))
    )
    (net (code "19") (name "/PWM_8") (class "Default")
      (node (ref "P47") (pin "9") (pinfunction "9_9") (pintype "passive"))
      (node (ref "R111") (pin "2") (pinfunction "2_2") (pintype "passive"))
      (node (ref "R99") (pin "1") (pinfunction "1_1") (pintype "passive"))
    )
    (net (code "20") (name "/PWM_8_OUT") (class "Default")
      (node (ref "D21") (pin "2") (pinfunction "A_2") (pintype "passive"))
      (node (ref "P39") (pin "1") (pinfunction "1_1") (pintype "passive"))
      (node (ref "Q49") (pin "3") (pinfunction "S_3") (pintype "passive"))
    )
    (net (code "21") (name "/PWM_9") (class "Default")
      (node (ref "P47") (pin "10") (pinfunction "10_10") (pintype "passive"))
      (node (ref "R101") (pin "1") (pinfunction "1_1") (pintype "passive"))
      (node (ref "R112") (pin "2") (pinfunction "2_2") (pintype "passive"))
    )
    (net (code "22") (name "/PWM_9_OUT") (class "Default")
      (node (ref "D22") (pin "2") (pinfunction "A_2") (pintype "passive"))
      (node (ref "P40") (pin "1") (pinfunction "1_1") (pintype "passive"))
      (node (ref "Q51") (pin "3") (pinfunction "S_3") (pintype "passive"))
    )
    (net (code "23") (name "/PWM_10") (class "Default")
      (node (ref "P47") (pin "11") (pinfunction "11_11") (pintype "passive"))
      (node (ref "R105") (pin "1") (pinfunction "1_1") (pintype "passive"))
      (node (ref "R113") (pin "2") (pinfunction "2_2") (pintype "passive"))
    )
    (net (code "24") (name "/PWM_10_OUT") (class "Default")
      (node (ref "D23") (pin "2") (pinfunction "A_2") (pintype "passive"))
      (node (ref "P41") (pin "1") (pinfunction "1_1") (pintype "passive"))
      (node (ref "Q53") (pin "3") (pinfunction "S_3") (pintype "passive"))
    )
    (net (code "25") (name "/PWM_11") (class "Default")
      (node (ref "P47") (pin "12") (pinfunction "12_12") (pintype "passive"))
      (node (ref "R107") (pin "1") (pinfunction "1_1") (pintype "passive"))
      (node (ref "R114") (pin "2") (pinfunction "2_2") (pintype "passive"))
    )
    (net (code "26") (name "/PWM_11_OUT") (class "Default")
      (node (ref "D24") (pin "2") (pinfunction "A_2") (pintype "passive"))
      (node (ref "P42") (pin "1") (pinfunction "1_1") (pintype "passive"))
      (node (ref "Q55") (pin "3") (pinfunction "S_3") (pintype "passive"))
    )
    (net (code "27") (name "/PWM_12") (class "Default")
      (node (ref "P47") (pin "13") (pinfunction "13_13") (pintype "passive"))
      (node (ref "R123") (pin "1") (pinfunction "1_1") (pintype "passive"))
      (node (ref "R135") (pin "2") (pinfunction "2_2") (pintype "passive"))
    )
    (net (code "28") (name "/PWM_12_OUT") (class "Default")
      (node (ref "D25") (pin "2") (pinfunction "A_2") (pintype "passive"))
      (node (ref "P43") (pin "1") (pinfunction "1_1") (pintype "passive"))
      (node (ref "Q69") (pin "3") (pinfunction "S_3") (pintype "passive"))
    )
    (net (code "29") (name "/PWM_13") (class "Default")
      (node (ref "P47") (pin "14") (pinfunction "14_14") (pintype "passive"))
      (node (ref "R125") (pin "1") (pinfunction "1_1") (pintype "passive"))
      (node (ref "R136") (pin "2") (pinfunction "2_2") (pintype "passive"))
    )
    (net (code "30") (name "/PWM_13_OUT") (class "Default")
      (node (ref "D26") (pin "2") (pinfunction "A_2") (pintype "passive"))
      (node (ref "P44") (pin "1") (pinfunction "1_1") (pintype "passive"))
      (node (ref "Q71") (pin "3") (pinfunction "S_3") (pintype "passive"))
    )
    (net (code "31") (name "/PWM_14") (class "Default")
      (node (ref "P47") (pin "15") (pinfunction "15_15") (pintype "passive"))
      (node (ref "R129") (pin "1") (pinfunction "1_1") (pintype "passive"))
      (node (ref "R137") (pin "2") (pinfunction "2_2") (pintype "passive"))
    )
    (net (code "32") (name "/PWM_14_OUT") (class "Default")
      (node (ref "D27") (pin "2") (pinfunction "A_2") (pintype "passive"))
      (node (ref "P45") (pin "1") (pinfunction "1_1") (pintype "passive"))
      (node (ref "Q73") (pin "3") (pinfunction "S_3") (pintype "passive"))
    )
    (net (code "33") (name "/PWM_15") (class "Default")
      (node (ref "P47") (pin "16") (pinfunction "16_16") (pintype "passive"))
      (node (ref "R131") (pin "1") (pinfunction "1_1") (pintype "passive"))
      (node (ref "R138") (pin "2") (pinfunction "2_2") (pintype "passive"))
    )
    (net (code "34") (name "/PWM_15_OUT") (class "Default")
      (node (ref "D28") (pin "2") (pinfunction "A_2") (pintype "passive"))
      (node (ref "P46") (pin "1") (pinfunction "1_1") (pintype "passive"))
      (node (ref "Q75") (pin "3") (pinfunction "S_3") (pintype "passive"))
    )
    (net (code "35") (name "Net-(D13-K)") (class "Default")
      (node (ref "D13") (pin "1") (pinfunction "K_1") (pintype "passive"))
      (node (ref "Q9") (pin "1") (pinfunction "G_1") (pintype "passive"))
      (node (ref "R55") (pin "2") (pinfunction "2_2") (pintype "passive"))
    )
    (net (code "36") (name "Net-(D14-K)") (class "Default")
      (node (ref "D14") (pin "1") (pinfunction "K_1") (pintype "passive"))
      (node (ref "Q11") (pin "1") (pinfunction "G_1") (pintype "passive"))
      (node (ref "R56") (pin "2") (pinfunction "2_2") (pintype "passive"))
    )
    (net (code "37") (name "Net-(D15-K)") (class "Default")
      (node (ref "D15") (pin "1") (pinfunction "K_1") (pintype "passive"))
      (node (ref "Q13") (pin "1") (pinfunction "G_1") (pintype "passive"))
      (node (ref "R61") (pin "2") (pinfunction "2_2") (pintype "passive"))
    )
    (net (code "38") (name "Net-(D16-K)") (class "Default")
      (node (ref "D16") (pin "1") (pinfunction "K_1") (pintype "passive"))
      (node (ref "Q15") (pin "1") (pinfunction "G_1") (pintype "passive"))
      (node (ref "R62") (pin "2") (pinfunction "2_2") (pintype "passive"))
    )
    (net (code "39") (name "Net-(D17-K)") (class "Default")
      (node (ref "D17") (pin "1") (pinfunction "K_1") (pintype "passive"))
      (node (ref "Q29") (pin "1") (pinfunction "G_1") (pintype "passive"))
      (node (ref "R79") (pin "2") (pinfunction "2_2") (pintype "passive"))
    )
    (net (code "40") (name "Net-(D18-K)") (class "Default")
      (node (ref "D18") (pin "1") (pinfunction "K_1") (pintype "passive"))
      (node (ref "Q31") (pin "1") (pinfunction "G_1") (pintype "passive"))
      (node (ref "R80") (pin "2") (pinfunction "2_2") (pintype "passive"))
    )
    (net (code "41") (name "Net-(D19-K)") (class "Default")
      (node (ref "D19") (pin "1") (pinfunction "K_1") (pintype "passive"))
      (node (ref "Q33") (pin "1") (pinfunction "G_1") (pintype "passive"))
      (node (ref "R85") (pin "2") (pinfunction "2_2") (pintype "passive"))
    )
    (net (code "42") (name "Net-(D20-K)") (class "Default")
      (node (ref "D20") (pin "1") (pinfunction "K_1") (pintype "passive"))
      (node (ref "Q35") (pin "1") (pinfunction "G_1") (pintype "passive"))
      (node (ref "R86") (pin "2") (pinfunction "2_2") (pintype "passive"))
    )
    (net (code "43") (name "Net-(D21-K)") (class "Default")
      (node (ref "D21") (pin "1") (pinfunction "K_1") (pintype "passive"))
      (node (ref "Q49") (pin "1") (pinfunction "G_1") (pintype "passive"))
      (node (ref "R103") (pin "2") (pinfunction "2_2") (pintype "passive"))
    )
    (net (code "44") (name "Net-(D22-K)") (class "Default")
      (node (ref "D22") (pin "1") (pinfunction "K_1") (pintype "passive"))
      (node (ref "Q51") (pin "1") (pinfunction "G_1") (pintype "passive"))
      (node (ref "R104") (pin "2") (pinfunction "2_2") (pintype "passive"))
    )
    (net (code "45") (name "Net-(D23-K)") (class "Default")
      (node (ref "D23") (pin "1") (pinfunction "K_1") (pintype "passive"))
      (node (ref "Q53") (pin "1") (pinfunction "G_1") (pintype "passive"))
      (node (ref "R109") (pin "2") (pinfunction "2_2") (pintype "passive"))
    )
    (net (code "46") (name "Net-(D24-K)") (class "Default")
      (node (ref "D24") (pin "1") (pinfunction "K_1") (pintype "passive"))
      (node (ref "Q55") (pin "1") (pinfunction "G_1") (pintype "passive"))
      (node (ref "R110") (pin "2") (pinfunction "2_2") (pintype "passive"))
    )
    (net (code "47") (name "Net-(D25-K)") (class "Default")
      (node (ref "D25") (pin "1") (pinfunction "K_1") (pintype "passive"))
      (node (ref "Q69") (pin "1") (pinfunction "G_1") (pintype "passive"))
      (node (ref "R127") (pin "2") (pinfunction "2_2") (pintype "passive"))
    )
    (net (code "48") (name "Net-(D26-K)") (class "Default")
      (node (ref "D26") (pin "1") (pinfunction "K_1") (pintype "passive"))
      (node (ref "Q71") (pin "1") (pinfunction "G_1") (pintype "passive"))
      (node (ref "R128") (pin "2") (pinfunction "2_2") (pintype "passive"))
    )
    (net (code "49") (name "Net-(D27-K)") (class "Default")
      (node (ref "D27") (pin "1") (pinfunction "K_1") (pintype "passive"))
      (node (ref "Q73") (pin "1") (pinfunction "G_1") (pintype "passive"))
      (node (ref "R133") (pin "2") (pinfunction "2_2") (pintype "passive"))
    )
    (net (code "50") (name "Net-(D28-K)") (class "Default")
      (node (ref "D28") (pin "1") (pinfunction "K_1") (pintype "passive"))
      (node (ref "Q75") (pin "1") (pinfunction "G_1") (pintype "passive"))
      (node (ref "R134") (pin "2") (pinfunction "2_2") (pintype "passive"))
    )
    (net (code "51") (name "Net-(Q8-B)") (class "Default")
      (node (ref "Q8") (pin "1") (pinfunction "B_1") (pintype "passive"))
      (node (ref "R51") (pin "2") (pinfunction "2_2") (pintype "passive"))
    )
    (net (code "52") (name "Net-(Q10-B)") (class "Default")
      (node (ref "Q10") (pin "1") (pinfunction "B_1") (pintype "passive"))
      (node (ref "R53") (pin "2") (pinfunction "2_2") (pintype "passive"))
    )
    (net (code "53") (name "Net-(Q10-C)") (class "Default")
      (node (ref "Q10") (pin "3") (pinfunction "C_3") (pintype "passive"))
      (node (ref "Q19") (pin "1") (pinfunction "G_1") (pintype "passive"))
      (node (ref "R68") (pin "1") (pinfunction "1_1") (pintype "passive"))
    )
    (net (code "54") (name "Net-(Q12-B)") (class "Default")
      (node (ref "Q12") (pin "1") (pinfunction "B_1") (pintype "passive"))
      (node (ref "R57") (pin "2") (pinfunction "2_2") (pintype "passive"))
    )
    (net (code "55") (name "Net-(Q12-C)") (class "Default")
      (node (ref "Q12") (pin "3") (pinfunction "C_3") (pintype "passive"))
      (node (ref "Q20") (pin "1") (pinfunction "G_1") (pintype "passive"))
      (node (ref "R69") (pin "1") (pinfunction "1_1") (pintype "passive"))
    )
    (net (code "56") (name "Net-(Q14-B)") (class "Default")
      (node (ref "Q14") (pin "1") (pinfunction "B_1") (pintype "passive"))
      (node (ref "R59") (pin "2") (pinfunction "2_2") (pintype "passive"))
    )
    (net (code "57") (name "Net-(Q14-C)") (class "Default")
      (node (ref "Q14") (pin "3") (pinfunction "C_3") (pintype "passive"))
      (node (ref "Q21") (pin "1") (pinfunction "G_1") (pintype "passive"))
      (node (ref "R70") (pin "1") (pinfunction "1_1") (pintype "passive"))
    )
    (net (code "58") (name "Net-(Q16-B)") (class "Default")
      (node (ref "Q16") (pin "1") (pinfunction "B_1") (pintype "passive"))
      (node (ref "Q5") (pin "1") (pinfunction "B_1") (pintype "passive"))
      (node (ref "R54") (pin "1") (pinfunction "1_1") (pintype "passive"))
    )
    (net (code "59") (name "Net-(Q16-E)") (class "Default")
      (node (ref "Q16") (pin "2") (pinfunction "E_2") (pintype "passive"))
      (node (ref "Q5") (pin "2") (pinfunction "E_2") (pintype "passive"))
      (node (ref "R56") (pin "1") (pinfunction "1_1") (pintype "passive"))
    )
    (net (code "60") (name "Net-(Q17-B)") (class "Default")
      (node (ref "Q17") (pin "1") (pinfunction "B_1") (pintype "passive"))
      (node (ref "Q6") (pin "1") (pinfunction "B_1") (pintype "passive"))
      (node (ref "R58") (pin "1") (pinfunction "1_1") (pintype "passive"))
    )
    (net (code "61") (name "Net-(Q17-E)") (class "Default")
      (node (ref "Q17") (pin "2") (pinfunction "E_2") (pintype "passive"))
      (node (ref "Q6") (pin "2") (pinfunction "E_2") (pintype "passive"))
      (node (ref "R61") (pin "1") (pinfunction "1_1") (pintype "passive"))
    )
    (net (code "62") (name "Net-(Q18-D)") (class "Default")
      (node (ref "Q18") (pin "3") (pinfunction "D_3") (pintype "passive"))
      (node (ref "R47") (pin "1") (pinfunction "1_1") (pintype "passive"))
      (node (ref "R52") (pin "2") (pinfunction "2_2") (pintype "passive"))
    )
    (net (code "63") (name "Net-(Q18-G)") (class "Default")
      (node (ref "Q18") (pin "1") (pinfunction "G_1") (pintype "passive"))
      (node (ref "Q8") (pin "3") (pinfunction "C_3") (pintype "passive"))
      (node (ref "R67") (pin "1") (pinfunction "1_1") (pintype "passive"))
    )
    (net (code "64") (name "Net-(Q19-D)") (class "Default")
      (node (ref "Q19") (pin "3") (pinfunction "D_3") (pintype "passive"))
      (node (ref "R48") (pin "1") (pinfunction "1_1") (pintype "passive"))
      (node (ref "R54") (pin "2") (pinfunction "2_2") (pintype "passive"))
    )
    (net (code "65") (name "Net-(Q20-D)") (class "Default")
      (node (ref "Q20") (pin "3") (pinfunction "D_3") (pintype "passive"))
      (node (ref "R49") (pin "1") (pinfunction "1_1") (pintype "passive"))
      (node (ref "R58") (pin "2") (pinfunction "2_2") (pintype "passive"))
    )
    (net (code "66") (name "Net-(Q21-D)") (class "Default")
      (node (ref "Q21") (pin "3") (pinfunction "D_3") (pintype "passive"))
      (node (ref "R50") (pin "1") (pinfunction "1_1") (pintype "passive"))
      (node (ref "R60") (pin "2") (pinfunction "2_2") (pintype "passive"))
    )
    (net (code "67") (name "Net-(Q22-B)") (class "Default")
      (node (ref "Q22") (pin "1") (pinfunction "B_1") (pintype "passive"))
      (node (ref "Q4") (pin "1") (pinfunction "B_1") (pintype "passive"))
      (node (ref "R52") (pin "1") (pinfunction "1_1") (pintype "passive"))
    )
    (net (code "68") (name "Net-(Q22-E)") (class "Default")
      (node (ref "Q22") (pin "2") (pinfunction "E_2") (pintype "passive"))
      (node (ref "Q4") (pin "2") (pinfunction "E_2") (pintype "passive"))
      (node (ref "R55") (pin "1") (pinfunction "1_1") (pintype "passive"))
    )
    (net (code "69") (name "Net-(Q23-B)") (class "Default")
      (node (ref "Q23") (pin "1") (pinfunction "B_1") (pintype "passive"))
      (node (ref "Q7") (pin "1") (pinfunction "B_1") (pintype "passive"))
      (node (ref "R60") (pin "1") (pinfunction "1_1") (pintype "passive"))
    )
    (net (code "70") (name "Net-(Q23-E)") (class "Default")
      (node (ref "Q23") (pin "2") (pinfunction "E_2") (pintype "passive"))
      (node (ref "Q7") (pin "2") (pinfunction "E_2") (pintype "passive"))
      (node (ref "R62") (pin "1") (pinfunction "1_1") (pintype "passive"))
    )
    (net (code "71") (name "Net-(Q24-B)") (class "Default")
      (node (ref "Q24") (pin "1") (pinfunction "B_1") (pintype "passive"))
      (node (ref "Q40") (pin "1") (pinfunction "B_1") (pintype "passive"))
      (node (ref "R76") (pin "1") (pinfunction "1_1") (pintype "passive"))
    )
    (net (code "72") (name "Net-(Q24-E)") (class "Default")
      (node (ref "Q24") (pin "2") (pinfunction "E_2") (pintype "passive"))
      (node (ref "Q40") (pin "2") (pinfunction "E_2") (pintype "passive"))
      (node (ref "R79") (pin "1") (pinfunction "1_1") (pintype "passive"))
    )
    (net (code "73") (name "Net-(Q25-B)") (class "Default")
      (node (ref "Q25") (pin "1") (pinfunction "B_1") (pintype "passive"))
      (node (ref "Q41") (pin "1") (pinfunction "B_1") (pintype "passive"))
      (node (ref "R78") (pin "1") (pinfunction "1_1") (pintype "passive"))
    )
    (net (code "74") (name "Net-(Q25-E)") (class "Default")
      (node (ref "Q25") (pin "2") (pinfunction "E_2") (pintype "passive"))
      (node (ref "Q41") (pin "2") (pinfunction "E_2") (pintype "passive"))
      (node (ref "R80") (pin "1") (pinfunction "1_1") (pintype "passive"))
    )
    (net (code "75") (name "Net-(Q26-B)") (class "Default")
      (node (ref "Q26") (pin "1") (pinfunction "B_1") (pintype "passive"))
      (node (ref "Q42") (pin "1") (pinfunction "B_1") (pintype "passive"))
      (node (ref "R82") (pin "1") (pinfunction "1_1") (pintype "passive"))
    )
    (net (code "76") (name "Net-(Q26-E)") (class "Default")
      (node (ref "Q26") (pin "2") (pinfunction "E_2") (pintype "passive"))
      (node (ref "Q42") (pin "2") (pinfunction "E_2") (pintype "passive"))
      (node (ref "R85") (pin "1") (pinfunction "1_1") (pintype "passive"))
    )
    (net (code "77") (name "Net-(Q27-B)") (class "Default")
      (node (ref "Q27") (pin "1") (pinfunction "B_1") (pintype "passive"))
      (node (ref "Q43") (pin "1") (pinfunction "B_1") (pintype "passive"))
      (node (ref "R84") (pin "1") (pinfunction "1_1") (pintype "passive"))
    )
    (net (code "78") (name "Net-(Q27-E)") (class "Default")
      (node (ref "Q27") (pin "2") (pinfunction "E_2") (pintype "passive"))
      (node (ref "Q43") (pin "2") (pinfunction "E_2") (pintype "passive"))
      (node (ref "R86") (pin "1") (pinfunction "1_1") (pintype "passive"))
    )
    (net (code "79") (name "Net-(Q28-B)") (class "Default")
      (node (ref "Q28") (pin "1") (pinfunction "B_1") (pintype "passive"))
      (node (ref "R75") (pin "2") (pinfunction "2_2") (pintype "passive"))
    )
    (net (code "80") (name "Net-(Q28-C)") (class "Default")
      (node (ref "Q28") (pin "3") (pinfunction "C_3") (pintype "passive"))
      (node (ref "Q36") (pin "1") (pinfunction "G_1") (pintype "passive"))
      (node (ref "R91") (pin "1") (pinfunction "1_1") (pintype "passive"))
    )
    (net (code "81") (name "Net-(Q30-B)") (class "Default")
      (node (ref "Q30") (pin "1") (pinfunction "B_1") (pintype "passive"))
      (node (ref "R77") (pin "2") (pinfunction "2_2") (pintype "passive"))
    )
    (net (code "82") (name "Net-(Q30-C)") (class "Default")
      (node (ref "Q30") (pin "3") (pinfunction "C_3") (pintype "passive"))
      (node (ref "Q37") (pin "1") (pinfunction "G_1") (pintype "passive"))
      (node (ref "R92") (pin "1") (pinfunction "1_1") (pintype "passive"))
    )
    (net (code "83") (name "Net-(Q32-B)") (class "Default")
      (node (ref "Q32") (pin "1") (pinfunction "B_1") (pintype "passive"))
      (node (ref "R81") (pin "2") (pinfunction "2_2") (pintype "passive"))
    )
    (net (code "84") (name "Net-(Q32-C)") (class "Default")
      (node (ref "Q32") (pin "3") (pinfunction "C_3") (pintype "passive"))
      (node (ref "Q38") (pin "1") (pinfunction "G_1") (pintype "passive"))
      (node (ref "R93") (pin "1") (pinfunction "1_1") (pintype "passive"))
    )
    (net (code "85") (name "Net-(Q34-B)") (class "Default")
      (node (ref "Q34") (pin "1") (pinfunction "B_1") (pintype "passive"))
      (node (ref "R83") (pin "2") (pinfunction "2_2") (pintype "passive"))
    )
    (net (code "86") (name "Net-(Q34-C)") (class "Default")
      (node (ref "Q34") (pin "3") (pinfunction "C_3") (pintype "passive"))
      (node (ref "Q39") (pin "1") (pinfunction "G_1") (pintype "passive"))
      (node (ref "R94") (pin "1") (pinfunction "1_1") (pintype "passive"))
    )
    (net (code "87") (name "Net-(Q36-D)") (class "Default")
      (node (ref "Q36") (pin "3") (pinfunction "D_3") (pintype "passive"))
      (node (ref "R71") (pin "1") (pinfunction "1_1") (pintype "passive"))
      (node (ref "R76") (pin "2") (pinfunction "2_2") (pintype "passive"))
    )
    (net (code "88") (name "Net-(Q37-D)") (class "Default")
      (node (ref "Q37") (pin "3") (pinfunction "D_3") (pintype "passive"))
      (node (ref "R72") (pin "1") (pinfunction "1_1") (pintype "passive"))
      (node (ref "R78") (pin "2") (pinfunction "2_2") (pintype "passive"))
    )
    (net (code "89") (name "Net-(Q38-D)") (class "Default")
      (node (ref "Q38") (pin "3") (pinfunction "D_3") (pintype "passive"))
      (node (ref "R73") (pin "1") (pinfunction "1_1") (pintype "passive"))
      (node (ref "R82") (pin "2") (pinfunction "2_2") (pintype "passive"))
    )
    (net (code "90") (name "Net-(Q39-D)") (class "Default")
      (node (ref "Q39") (pin "3") (pinfunction "D_3") (pintype "passive"))
      (node (ref "R74") (pin "1") (pinfunction "1_1") (pintype "passive"))
      (node (ref "R84") (pin "2") (pinfunction "2_2") (pintype "passive"))
    )
    (net (code "91") (name "Net-(Q44-B)") (class "Default")
      (node (ref "Q44") (pin "1") (pinfunction "B_1") (pintype "passive"))
      (node (ref "Q60") (pin "1") (pinfunction "B_1") (pintype "passive"))
      (node (ref "R100") (pin "1") (pinfunction "1_1") (pintype "passive"))
    )
    (net (code "92") (name "Net-(Q44-E)") (class "Default")
      (node (ref "Q44") (pin "2") (pinfunction "E_2") (pintype "passive"))
      (node (ref "Q60") (pin "2") (pinfunction "E_2") (pintype "passive"))
      (node (ref "R103") (pin "1") (pinfunction "1_1") (pintype "passive"))
    )
    (net (code "93") (name "Net-(Q45-B)") (class "Default")
      (node (ref "Q45") (pin "1") (pinfunction "B_1") (pintype "passive"))
      (node (ref "Q61") (pin "1") (pinfunction "B_1") (pintype "passive"))
      (node (ref "R102") (pin "1") (pinfunction "1_1") (pintype "passive"))
    )
    (net (code "94") (name "Net-(Q45-E)") (class "Default")
      (node (ref "Q45") (pin "2") (pinfunction "E_2") (pintype "passive"))
      (node (ref "Q61") (pin "2") (pinfunction "E_2") (pintype "passive"))
      (node (ref "R104") (pin "1") (pinfunction "1_1") (pintype "passive"))
    )
    (net (code "95") (name "Net-(Q46-B)") (class "Default")
      (node (ref "Q46") (pin "1") (pinfunction "B_1") (pintype "passive"))
      (node (ref "Q62") (pin "1") (pinfunction "B_1") (pintype "passive"))
      (node (ref "R106") (pin "1") (pinfunction "1_1") (pintype "passive"))
    )
    (net (code "96") (name "Net-(Q46-E)") (class "Default")
      (node (ref "Q46") (pin "2") (pinfunction "E_2") (pintype "passive"))
      (node (ref "Q62") (pin "2") (pinfunction "E_2") (pintype "passive"))
      (node (ref "R109") (pin "1") (pinfunction "1_1") (pintype "passive"))
    )
    (net (code "97") (name "Net-(Q47-B)") (class "Default")
      (node (ref "Q47") (pin "1") (pinfunction "B_1") (pintype "passive"))
      (node (ref "Q63") (pin "1") (pinfunction "B_1") (pintype "passive"))
      (node (ref "R108") (pin "1") (pinfunction "1_1") (pintype "passive"))
    )
    (net (code "98") (name "Net-(Q47-E)") (class "Default")
      (node (ref "Q47") (pin "2") (pinfunction "E_2") (pintype "passive"))
      (node (ref "Q63") (pin "2") (pinfunction "E_2") (pintype "passive"))
      (node (ref "R110") (pin "1") (pinfunction "1_1") (pintype "passive"))
    )
    (net (code "99") (name "Net-(Q48-B)") (class "Default")
      (node (ref "Q48") (pin "1") (pinfunction "B_1") (pintype "passive"))
      (node (ref "R99") (pin "2") (pinfunction "2_2") (pintype "passive"))
    )
    (net (code "100") (name "Net-(Q48-C)") (class "Default")
      (node (ref "Q48") (pin "3") (pinfunction "C_3") (pintype "passive"))
      (node (ref "Q56") (pin "1") (pinfunction "G_1") (pintype "passive"))
      (node (ref "R115") (pin "1") (pinfunction "1_1") (pintype "passive"))
    )
    (net (code "101") (name "Net-(Q50-B)") (class "Default")
      (node (ref "Q50") (pin "1") (pinfunction "B_1") (pintype "passive"))
      (node (ref "R101") (pin "2") (pinfunction "2_2") (pintype "passive"))
    )
    (net (code "102") (name "Net-(Q50-C)") (class "Default")
      (node (ref "Q50") (pin "3") (pinfunction "C_3") (pintype "passive"))
      (node (ref "Q57") (pin "1") (pinfunction "G_1") (pintype "passive"))
      (node (ref "R116") (pin "1") (pinfunction "1_1") (pintype "passive"))
    )
    (net (code "103") (name "Net-(Q52-B)") (class "Default")
      (node (ref "Q52") (pin "1") (pinfunction "B_1") (pintype "passive"))
      (node (ref "R105") (pin "2") (pinfunction "2_2") (pintype "passive"))
    )
    (net (code "104") (name "Net-(Q52-C)") (class "Default")
      (node (ref "Q52") (pin "3") (pinfunction "C_3") (pintype "passive"))
      (node (ref "Q58") (pin "1") (pinfunction "G_1") (pintype "passive"))
      (node (ref "R117") (pin "1") (pinfunction "1_1") (pintype "passive"))
    )
    (net (code "105") (name "Net-(Q54-B)") (class "Default")
      (node (ref "Q54") (pin "1") (pinfunction "B_1") (pintype "passive"))
      (node (ref "R107") (pin "2") (pinfunction "2_2") (pintype "passive"))
    )
    (net (code "106") (name "Net-(Q54-C)") (class "Default")
      (node (ref "Q54") (pin "3") (pinfunction "C_3") (pintype "passive"))
      (node (ref "Q59") (pin "1") (pinfunction "G_1") (pintype "passive"))
      (node (ref "R118") (pin "1") (pinfunction "1_1") (pintype "passive"))
    )
    (net (code "107") (name "Net-(Q56-D)") (class "Default")
      (node (ref "Q56") (pin "3") (pinfunction "D_3") (pintype "passive"))
      (node (ref "R100") (pin "2") (pinfunction "2_2") (pintype "passive"))
      (node (ref "R95") (pin "1") (pinfunction "1_1") (pintype "passive"))
    )
    (net (code "108") (name "Net-(Q57-D)") (class "Default")
      (node (ref "Q57") (pin "3") (pinfunction "D_3") (pintype "passive"))
      (node (ref "R102") (pin "2") (pinfunction "2_2") (pintype "passive"))
      (node (ref "R96") (pin "1") (pinfunction "1_1") (pintype "passive"))
    )
    (net (code "109") (name "Net-(Q58-D)") (class "Default")
      (node (ref "Q58") (pin "3") (pinfunction "D_3") (pintype "passive"))
      (node (ref "R106") (pin "2") (pinfunction "2_2") (pintype "passive"))
      (node (ref "R97") (pin "1") (pinfunction "1_1") (pintype "passive"))
    )
    (net (code "110") (name "Net-(Q59-D)") (class "Default")
      (node (ref "Q59") (pin "3") (pinfunction "D_3") (pintype "passive"))
      (node (ref "R108") (pin "2") (pinfunction "2_2") (pintype "passive"))
      (node (ref "R98") (pin "1") (pinfunction "1_1") (pintype "passive"))
    )
    (net (code "111") (name "Net-(Q64-B)") (class "Default")
      (node (ref "Q64") (pin "1") (pinfunction "B_1") (pintype "passive"))
      (node (ref "Q80") (pin "1") (pinfunction "B_1") (pintype "passive"))
      (node (ref "R124") (pin "1") (pinfunction "1_1") (pintype "passive"))
    )
    (net (code "112") (name "Net-(Q64-E)") (class "Default")
      (node (ref "Q64") (pin "2") (pinfunction "E_2") (pintype "passive"))
      (node (ref "Q80") (pin "2") (pinfunction "E_2") (pintype "passive"))
      (node (ref "R127") (pin "1") (pinfunction "1_1") (pintype "passive"))
    )
    (net (code "113") (name "Net-(Q65-B)") (class "Default")
      (node (ref "Q65") (pin "1") (pinfunction "B_1") (pintype "passive"))
      (node (ref "Q81") (pin "1") (pinfunction "B_1") (pintype "passive"))
      (node (ref "R126") (pin "1") (pinfunction "1_1") (pintype "passive"))
    )
    (net (code "114") (name "Net-(Q65-E)") (class "Default")
      (node (ref "Q65") (pin "2") (pinfunction "E_2") (pintype "passive"))
      (node (ref "Q81") (pin "2") (pinfunction "E_2") (pintype "passive"))
      (node (ref "R128") (pin "1") (pinfunction "1_1") (pintype "passive"))
    )
    (net (code "115") (name "Net-(Q66-B)") (class "Default")
      (node (ref "Q66") (pin "1") (pinfunction "B_1") (pintype "passive"))
      (node (ref "Q82") (pin "1") (pinfunction "B_1") (pintype "passive"))
      (node (ref "R130") (pin "1") (pinfunction "1_1") (pintype "passive"))
    )
    (net (code "116") (name "Net-(Q66-E)") (class "Default")
      (node (ref "Q66") (pin "2") (pinfunction "E_2") (pintype "passive"))
      (node (ref "Q82") (pin "2") (pinfunction "E_2") (pintype "passive"))
      (node (ref "R133") (pin "1") (pinfunction "1_1") (pintype "passive"))
    )
    (net (code "117") (name "Net-(Q67-B)") (class "Default")
      (node (ref "Q67") (pin "1") (pinfunction "B_1") (pintype "passive"))
      (node (ref "Q83") (pin "1") (pinfunction "B_1") (pintype "passive"))
      (node (ref "R132") (pin "1") (pinfunction "1_1") (pintype "passive"))
    )
    (net (code "118") (name "Net-(Q67-E)") (class "Default")
      (node (ref "Q67") (pin "2") (pinfunction "E_2") (pintype "passive"))
      (node (ref "Q83") (pin "2") (pinfunction "E_2") (pintype "passive"))
      (node (ref "R134") (pin "1") (pinfunction "1_1") (pintype "passive"))
    )
    (net (code "119") (name "Net-(Q68-B)") (class "Default")
      (node (ref "Q68") (pin "1") (pinfunction "B_1") (pintype "passive"))
      (node (ref "R123") (pin "2") (pinfunction "2_2") (pintype "passive"))
    )
    (net (code "120") (name "Net-(Q68-C)") (class "Default")
      (node (ref "Q68") (pin "3") (pinfunction "C_3") (pintype "passive"))
      (node (ref "Q76") (pin "1") (pinfunction "G_1") (pintype "passive"))
      (node (ref "R139") (pin "1") (pinfunction "1_1") (pintype "passive"))
    )
    (net (code "121") (name "Net-(Q70-B)") (class "Default")
      (node (ref "Q70") (pin "1") (pinfunction "B_1") (pintype "passive"))
      (node (ref "R125") (pin "2") (pinfunction "2_2") (pintype "passive"))
    )
    (net (code "122") (name "Net-(Q70-C)") (class "Default")
      (node (ref "Q70") (pin "3") (pinfunction "C_3") (pintype "passive"))
      (node (ref "Q77") (pin "1") (pinfunction "G_1") (pintype "passive"))
      (node (ref "R140") (pin "1") (pinfunction "1_1") (pintype "passive"))
    )
    (net (code "123") (name "Net-(Q72-B)") (class "Default")
      (node (ref "Q72") (pin "1") (pinfunction "B_1") (pintype "passive"))
      (node (ref "R129") (pin "2") (pinfunction "2_2") (pintype "passive"))
    )
    (net (code "124") (name "Net-(Q72-C)") (class "Default")
      (node (ref "Q72") (pin "3") (pinfunction "C_3") (pintype "passive"))
      (node (ref "Q78") (pin "1") (pinfunction "G_1") (pintype "passive"))
      (node (ref "R141") (pin "1") (pinfunction "1_1") (pintype "passive"))
    )
    (net (code "125") (name "Net-(Q74-B)") (class "Default")
      (node (ref "Q74") (pin "1") (pinfunction "B_1") (pintype "passive"))
      (node (ref "R131") (pin "2") (pinfunction "2_2") (pintype "passive"))
    )
    (net (code "126") (name "Net-(Q74-C)") (class "Default")
      (node (ref "Q74") (pin "3") (pinfunction "C_3") (pintype "passive"))
      (node (ref "Q79") (pin "1") (pinfunction "G_1") (pintype "passive"))
      (node (ref "R142") (pin "1") (pinfunction "1_1") (pintype "passive"))
    )
    (net (code "127") (name "Net-(Q76-D)") (class "Default")
      (node (ref "Q76") (pin "3") (pinfunction "D_3") (pintype "passive"))
      (node (ref "R119") (pin "1") (pinfunction "1_1") (pintype "passive"))
      (node (ref "R124") (pin "2") (pinfunction "2_2") (pintype "passive"))
    )
    (net (code "128") (name "Net-(Q77-D)") (class "Default")
      (node (ref "Q77") (pin "3") (pinfunction "D_3") (pintype "passive"))
      (node (ref "R120") (pin "1") (pinfunction "1_1") (pintype "passive"))
      (node (ref "R126") (pin "2") (pinfunction "2_2") (pintype "passive"))
    )
    (net (code "129") (name "Net-(Q78-D)") (class "Default")
      (node (ref "Q78") (pin "3") (pinfunction "D_3") (pintype "passive"))
      (node (ref "R121") (pin "1") (pinfunction "1_1") (pintype "passive"))
      (node (ref "R130") (pin "2") (pinfunction "2_2") (pintype "passive"))
    )
    (net (code "130") (name "Net-(Q79-D)") (class "Default")
      (node (ref "Q79") (pin "3") (pinfunction "D_3") (pintype "passive"))
      (node (ref "R122") (pin "1") (pinfunction "1_1") (pintype "passive"))
      (node (ref "R132") (pin "2") (pinfunction "2_2") (pintype "passive"))
    )
    (net (code "131") (name "VDR") (class "Default")
      (node (ref "C56") (pin "1") (pinfunction "1_1") (pintype "passive"))
      (node (ref "C57") (pin "2") (pinfunction "2_2") (pintype "passive"))
      (node (ref "C61") (pin "2") (pinfunction "2_2") (pintype "passive"))
      (node (ref "C62") (pin "2") (pinfunction "2_2") (pintype "passive"))
      (node (ref "C83") (pin "2") (pinfunction "2_2") (pintype "passive"))
      (node (ref "Q24") (pin "3") (pinfunction "C_3") (pintype "passive"))
      (node (ref "Q25") (pin "3") (pinfunction "C_3") (pintype "passive"))
      (node (ref "Q26") (pin "3") (pinfunction "C_3") (pintype "passive"))
      (node (ref "Q27") (pin "3") (pinfunction "C_3") (pintype "passive"))
      (node (ref "Q4") (pin "3") (pinfunction "C_3") (pintype "passive"))
      (node (ref "Q44") (pin "3") (pinfunction "C_3") (pintype "passive"))
      (node (ref "Q45") (pin "3") (pinfunction "C_3") (pintype "passive"))
      (node (ref "Q46") (pin "3") (pinfunction "C_3") (pintype "passive"))
      (node (ref "Q47") (pin "3") (pinfunction "C_3") (pintype "passive"))
      (node (ref "Q5") (pin "3") (pinfunction "C_3") (pintype "passive"))
      (node (ref "Q6") (pin "3") (pinfunction "C_3") (pintype "passive"))
      (node (ref "Q64") (pin "3") (pinfunction "C_3") (pintype "passive"))
      (node (ref "Q65") (pin "3") (pinfunction "C_3") (pintype "passive"))
      (node (ref "Q66") (pin "3") (pinfunction "C_3") (pintype "passive"))
      (node (ref "Q67") (pin "3") (pinfunction "C_3") (pintype "passive"))
      (node (ref "Q7") (pin "3") (pinfunction "C_3") (pintype "passive"))
      (node (ref "R119") (pin "2") (pinfunction "2_2") (pintype "passive"))
      (node (ref "R120") (pin "2") (pinfunction "2_2") (pintype "passive"))
      (node (ref "R121") (pin "2") (pinfunction "2_2") (pintype "passive"))
      (node (ref "R122") (pin "2") (pinfunction "2_2") (pintype "passive"))
      (node (ref "R47") (pin "2") (pinfunction "2_2") (pintype "passive"))
      (node (ref "R48") (pin "2") (pinfunction "2_2") (pintype "passive"))
      (node (ref "R49") (pin "2") (pinfunction "2_2") (pintype "passive"))
      (node (ref "R50") (pin "2") (pinfunction "2_2") (pintype "passive"))
      (node (ref "R71") (pin "2") (pinfunction "2_2") (pintype "passive"))
      (node (ref "R72") (pin "2") (pinfunction "2_2") (pintype "passive"))
      (node (ref "R73") (pin "2") (pinfunction "2_2") (pintype "passive"))
      (node (ref "R74") (pin "2") (pinfunction "2_2") (pintype "passive"))
      (node (ref "R95") (pin "2") (pinfunction "2_2") (pintype "passive"))
      (node (ref "R96") (pin "2") (pinfunction "2_2") (pintype "passive"))
      (node (ref "R97") (pin "2") (pinfunction "2_2") (pintype "passive"))
      (node (ref "R98") (pin "2") (pinfunction "2_2") (pintype "passive"))
      (node (ref "U17") (pin "4") (pinfunction "+Vo_4") (pintype "passive"))
      (node (ref "U18") (pin "4") (pinfunction "+Vo_4") (pintype "passive"))
    )
  )
)
